# serial.net
KiCad netlist of a schematic drawn in EAGLE
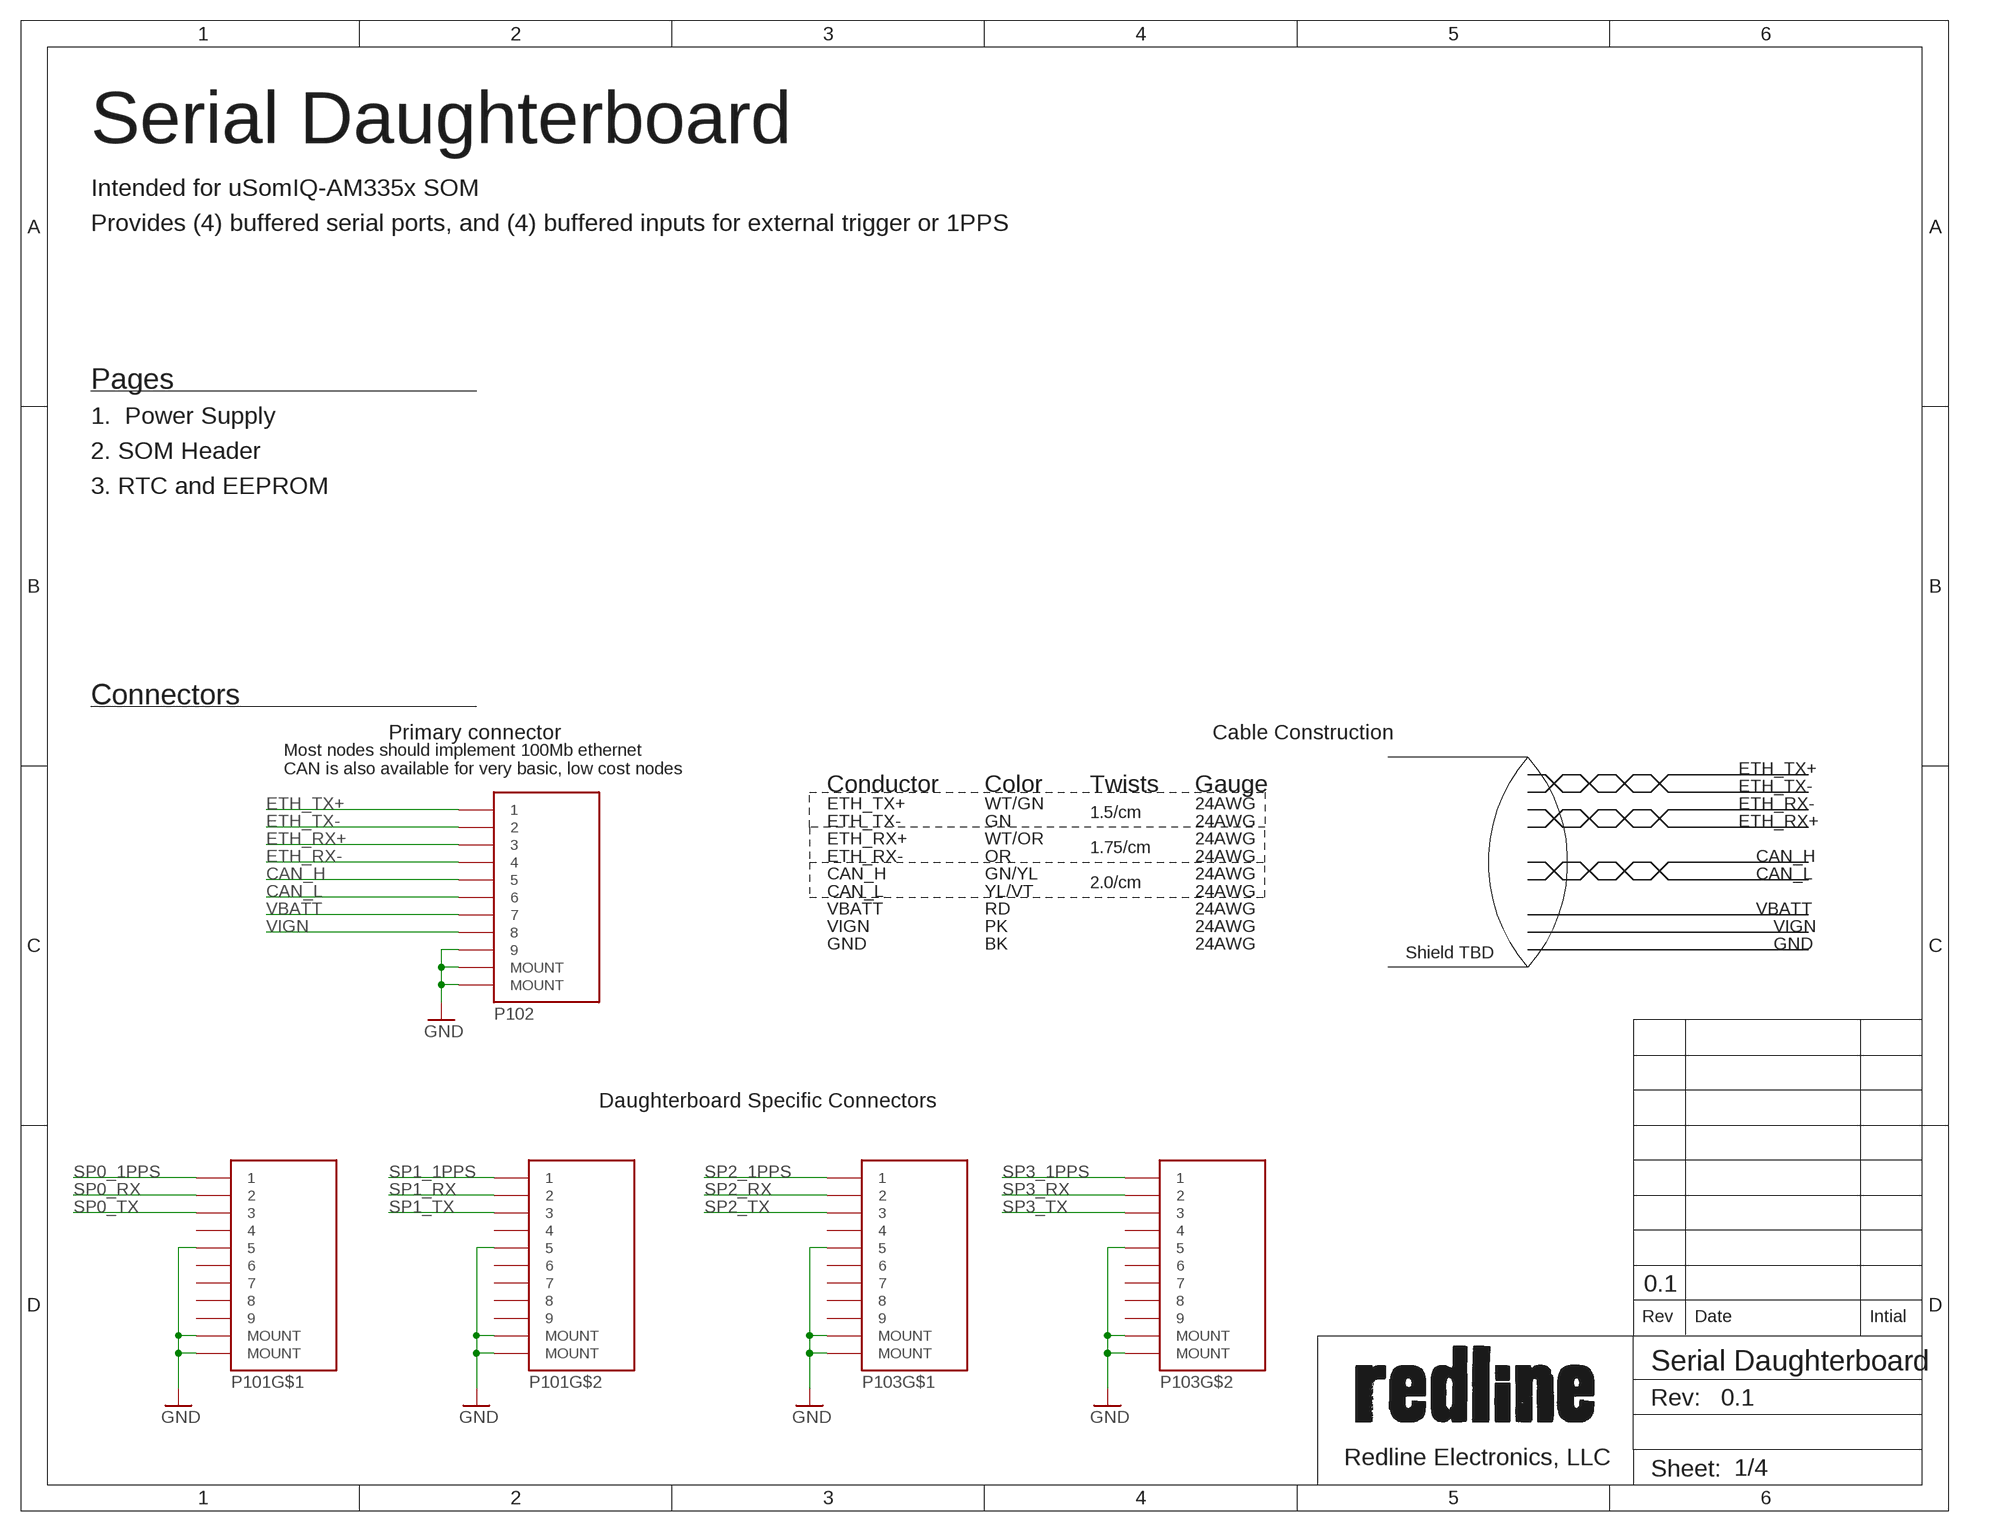
[diagram p0: schematic, sheet 1]
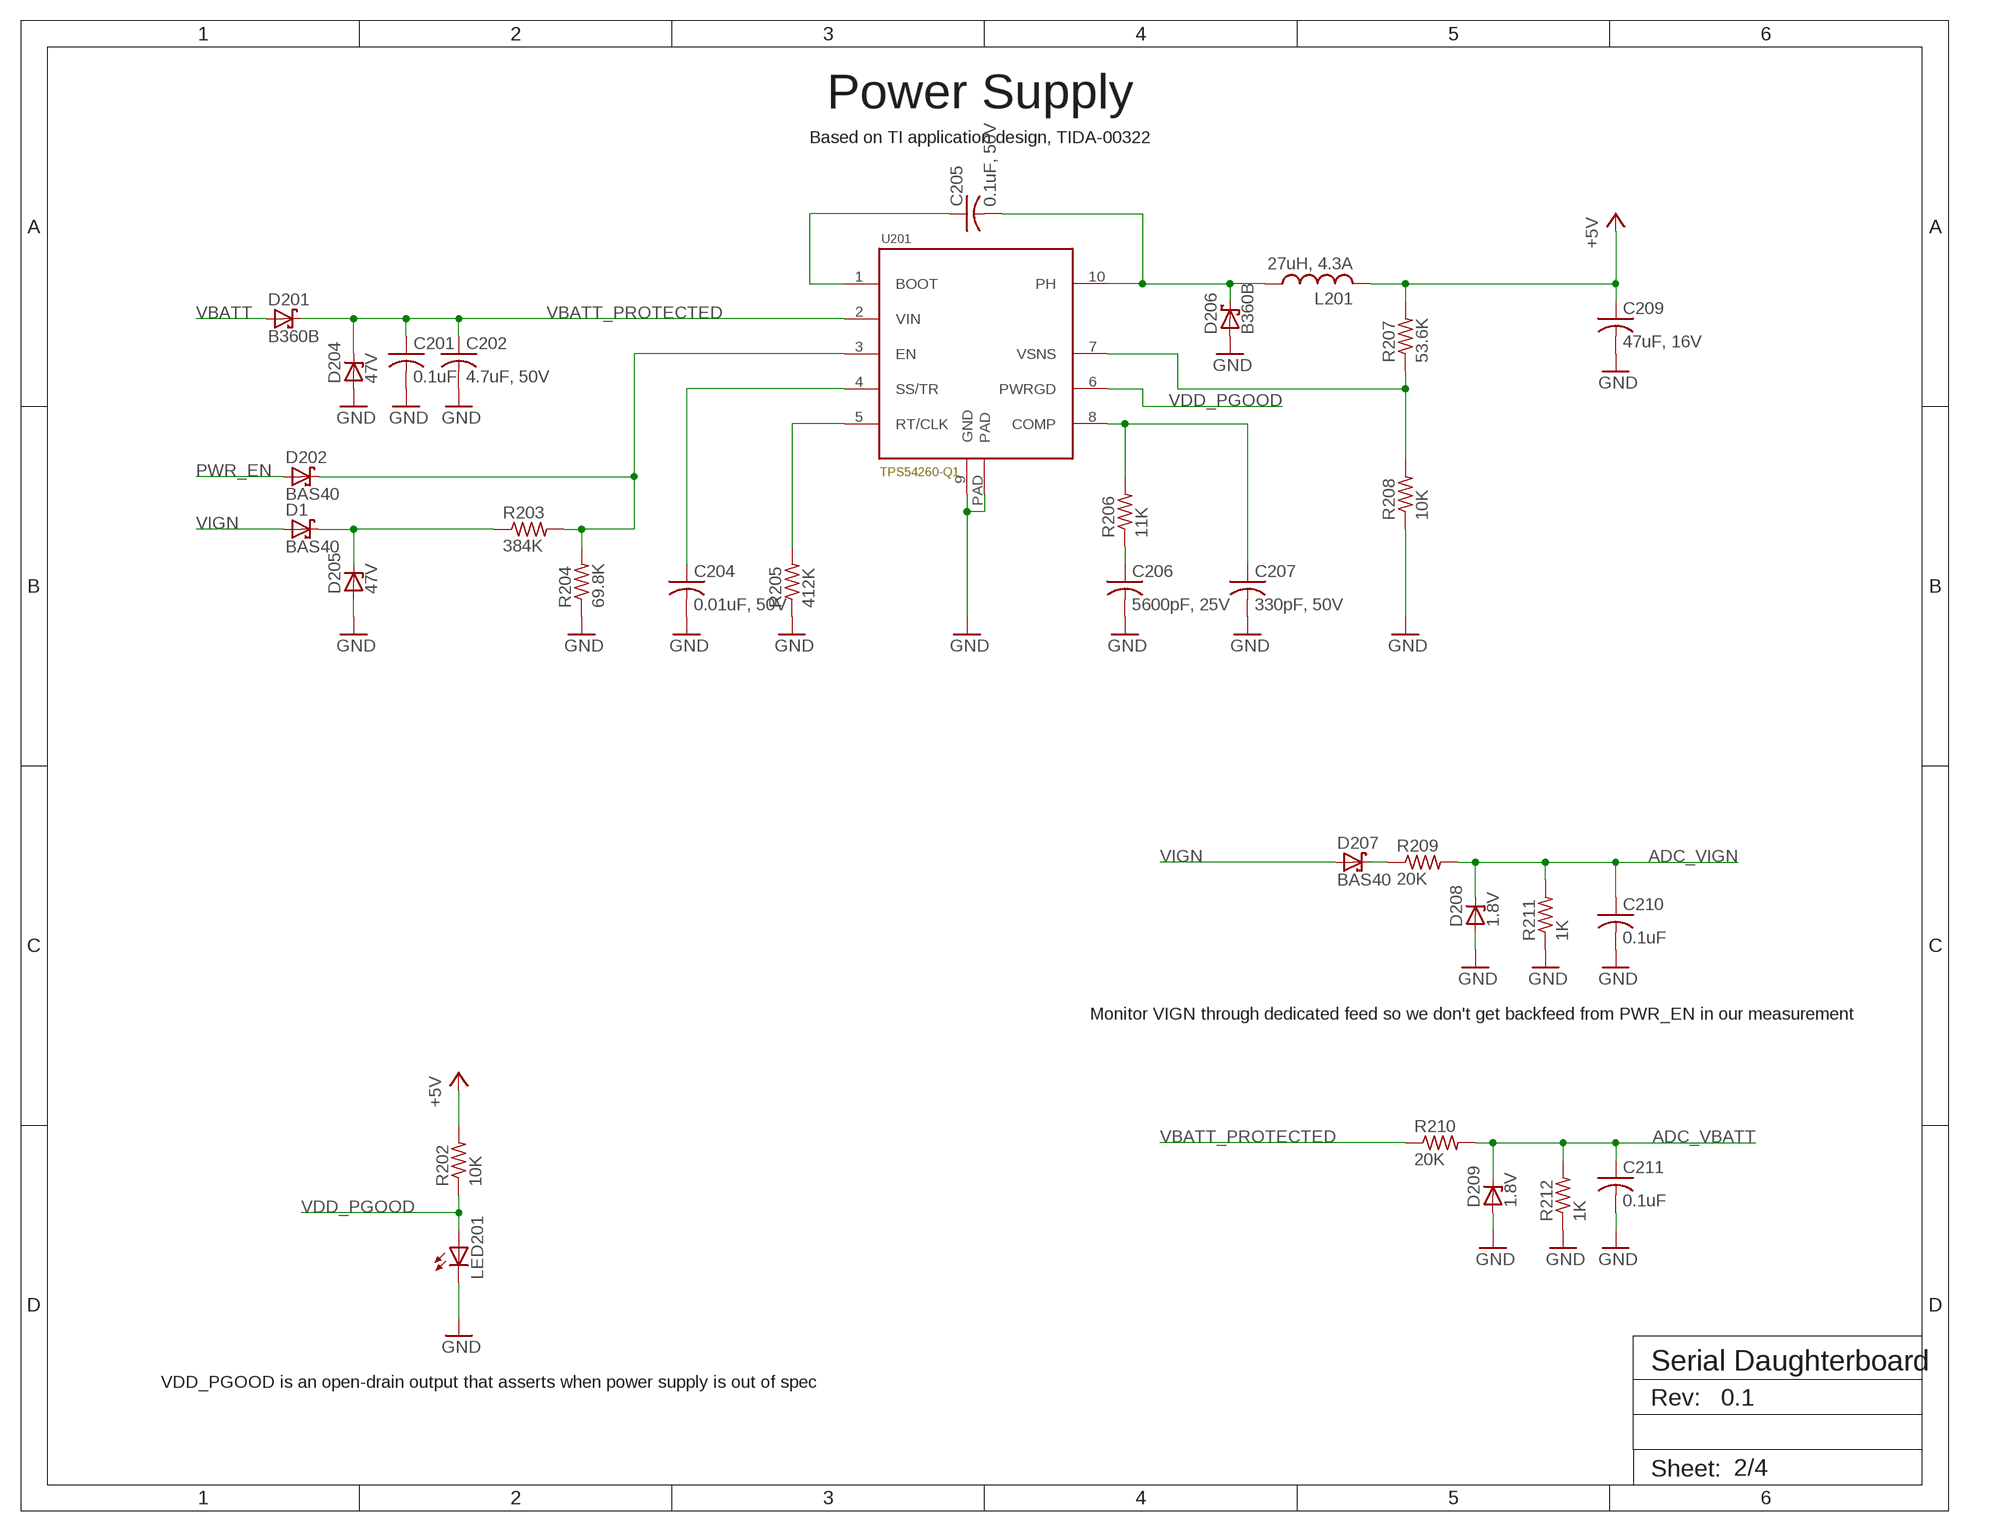
[diagram p1: schematic, sheet 2]
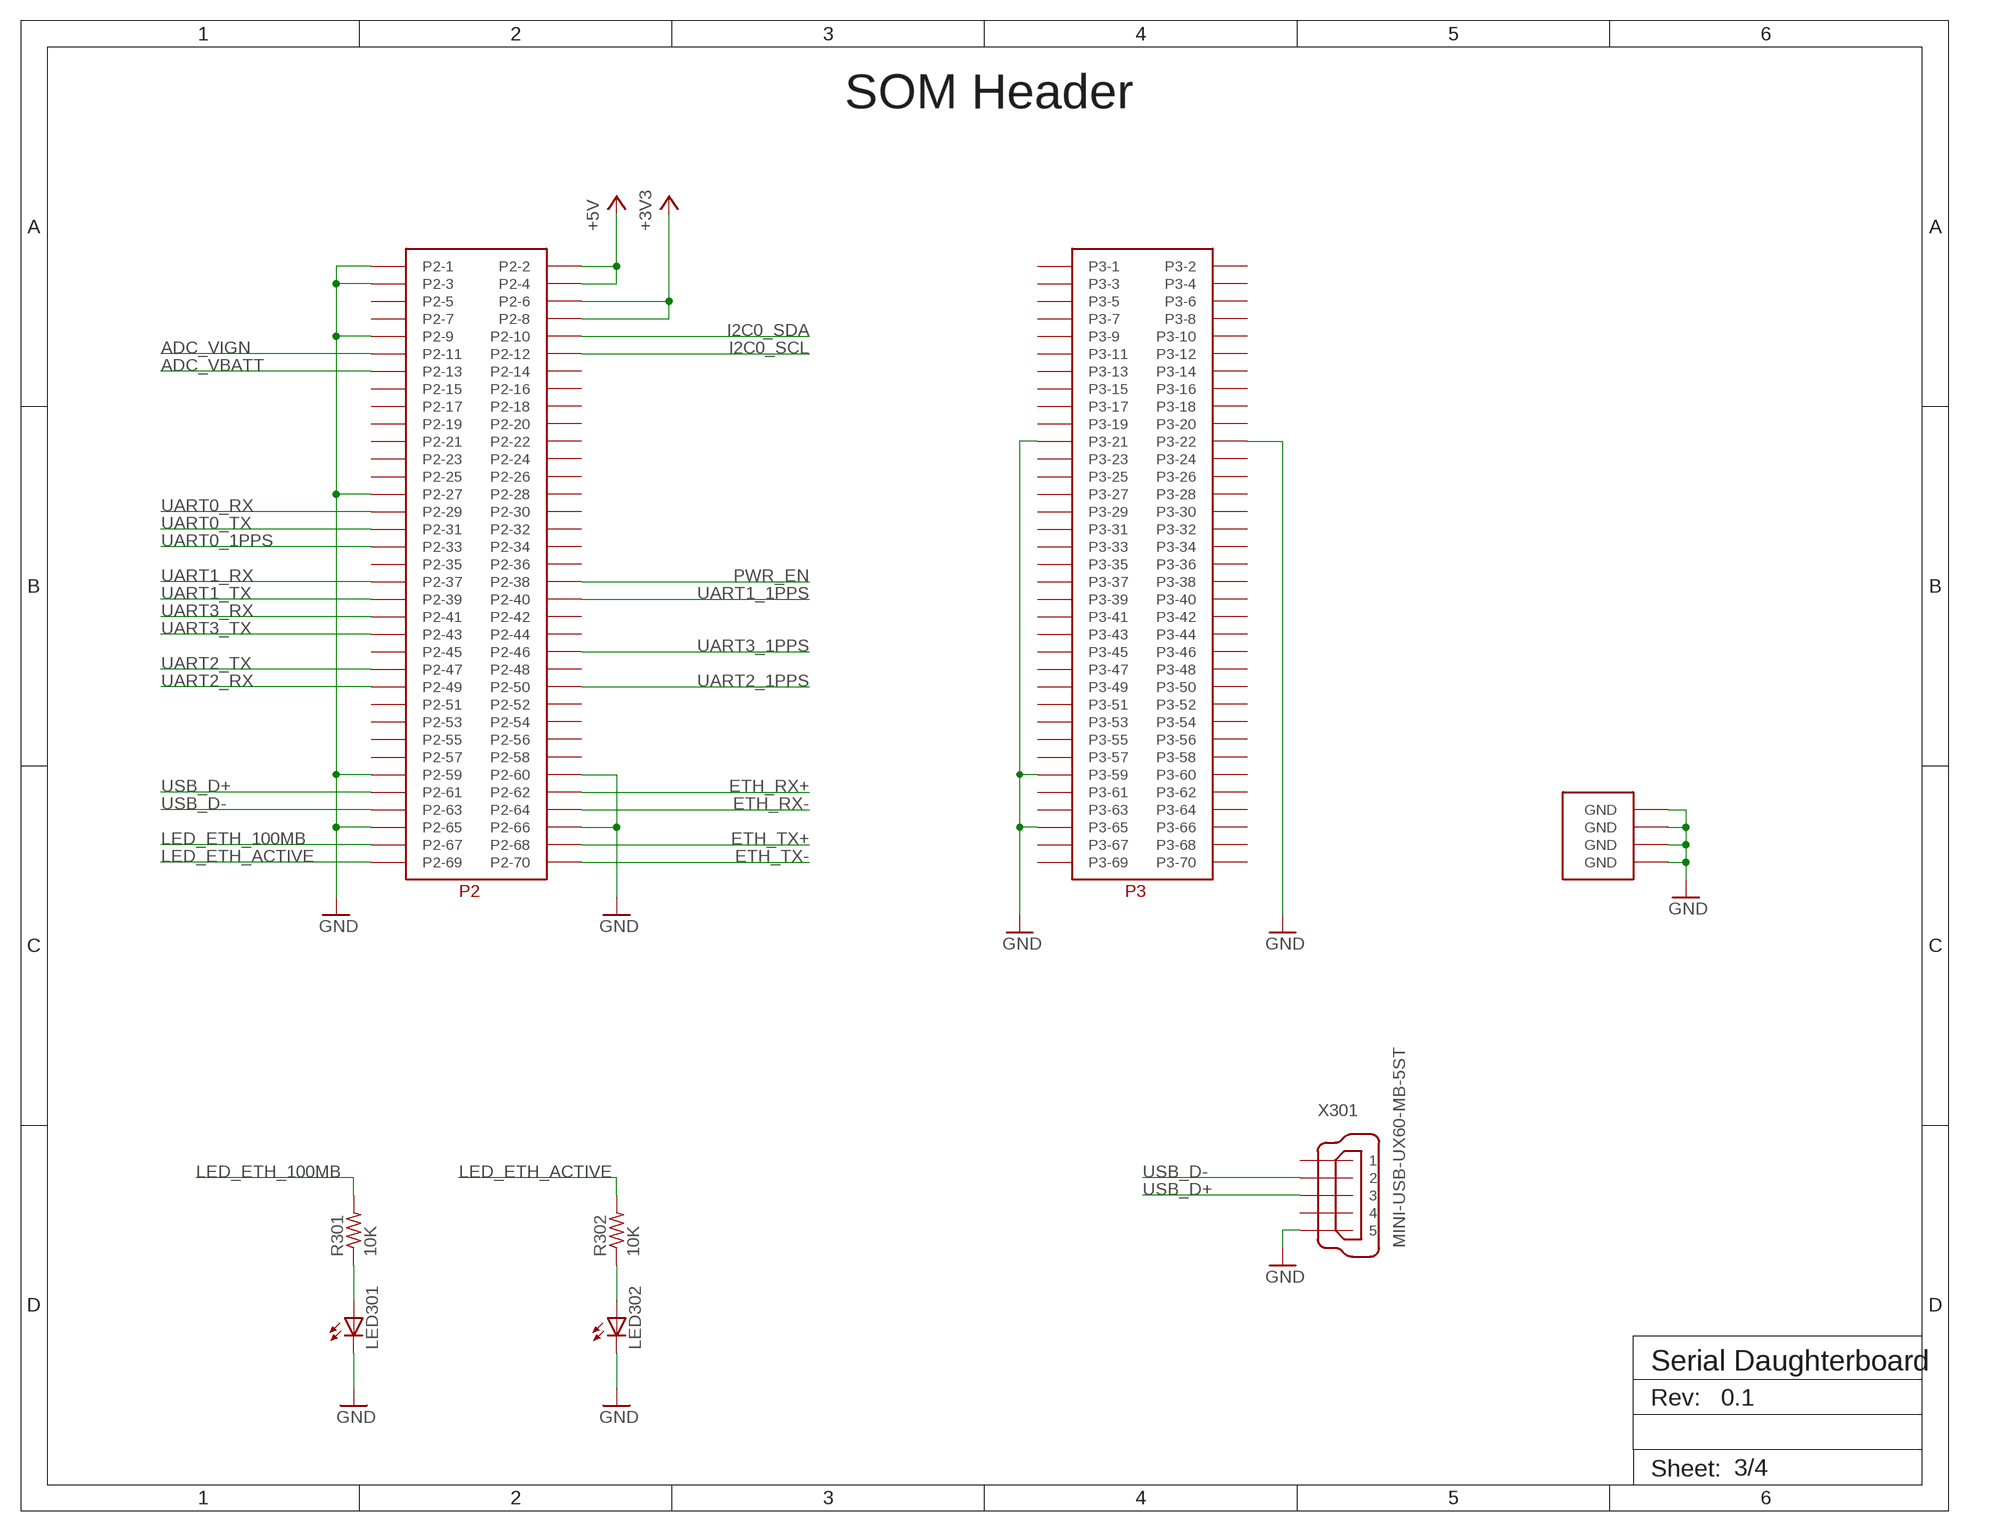
[diagram p2: schematic, sheet 3]
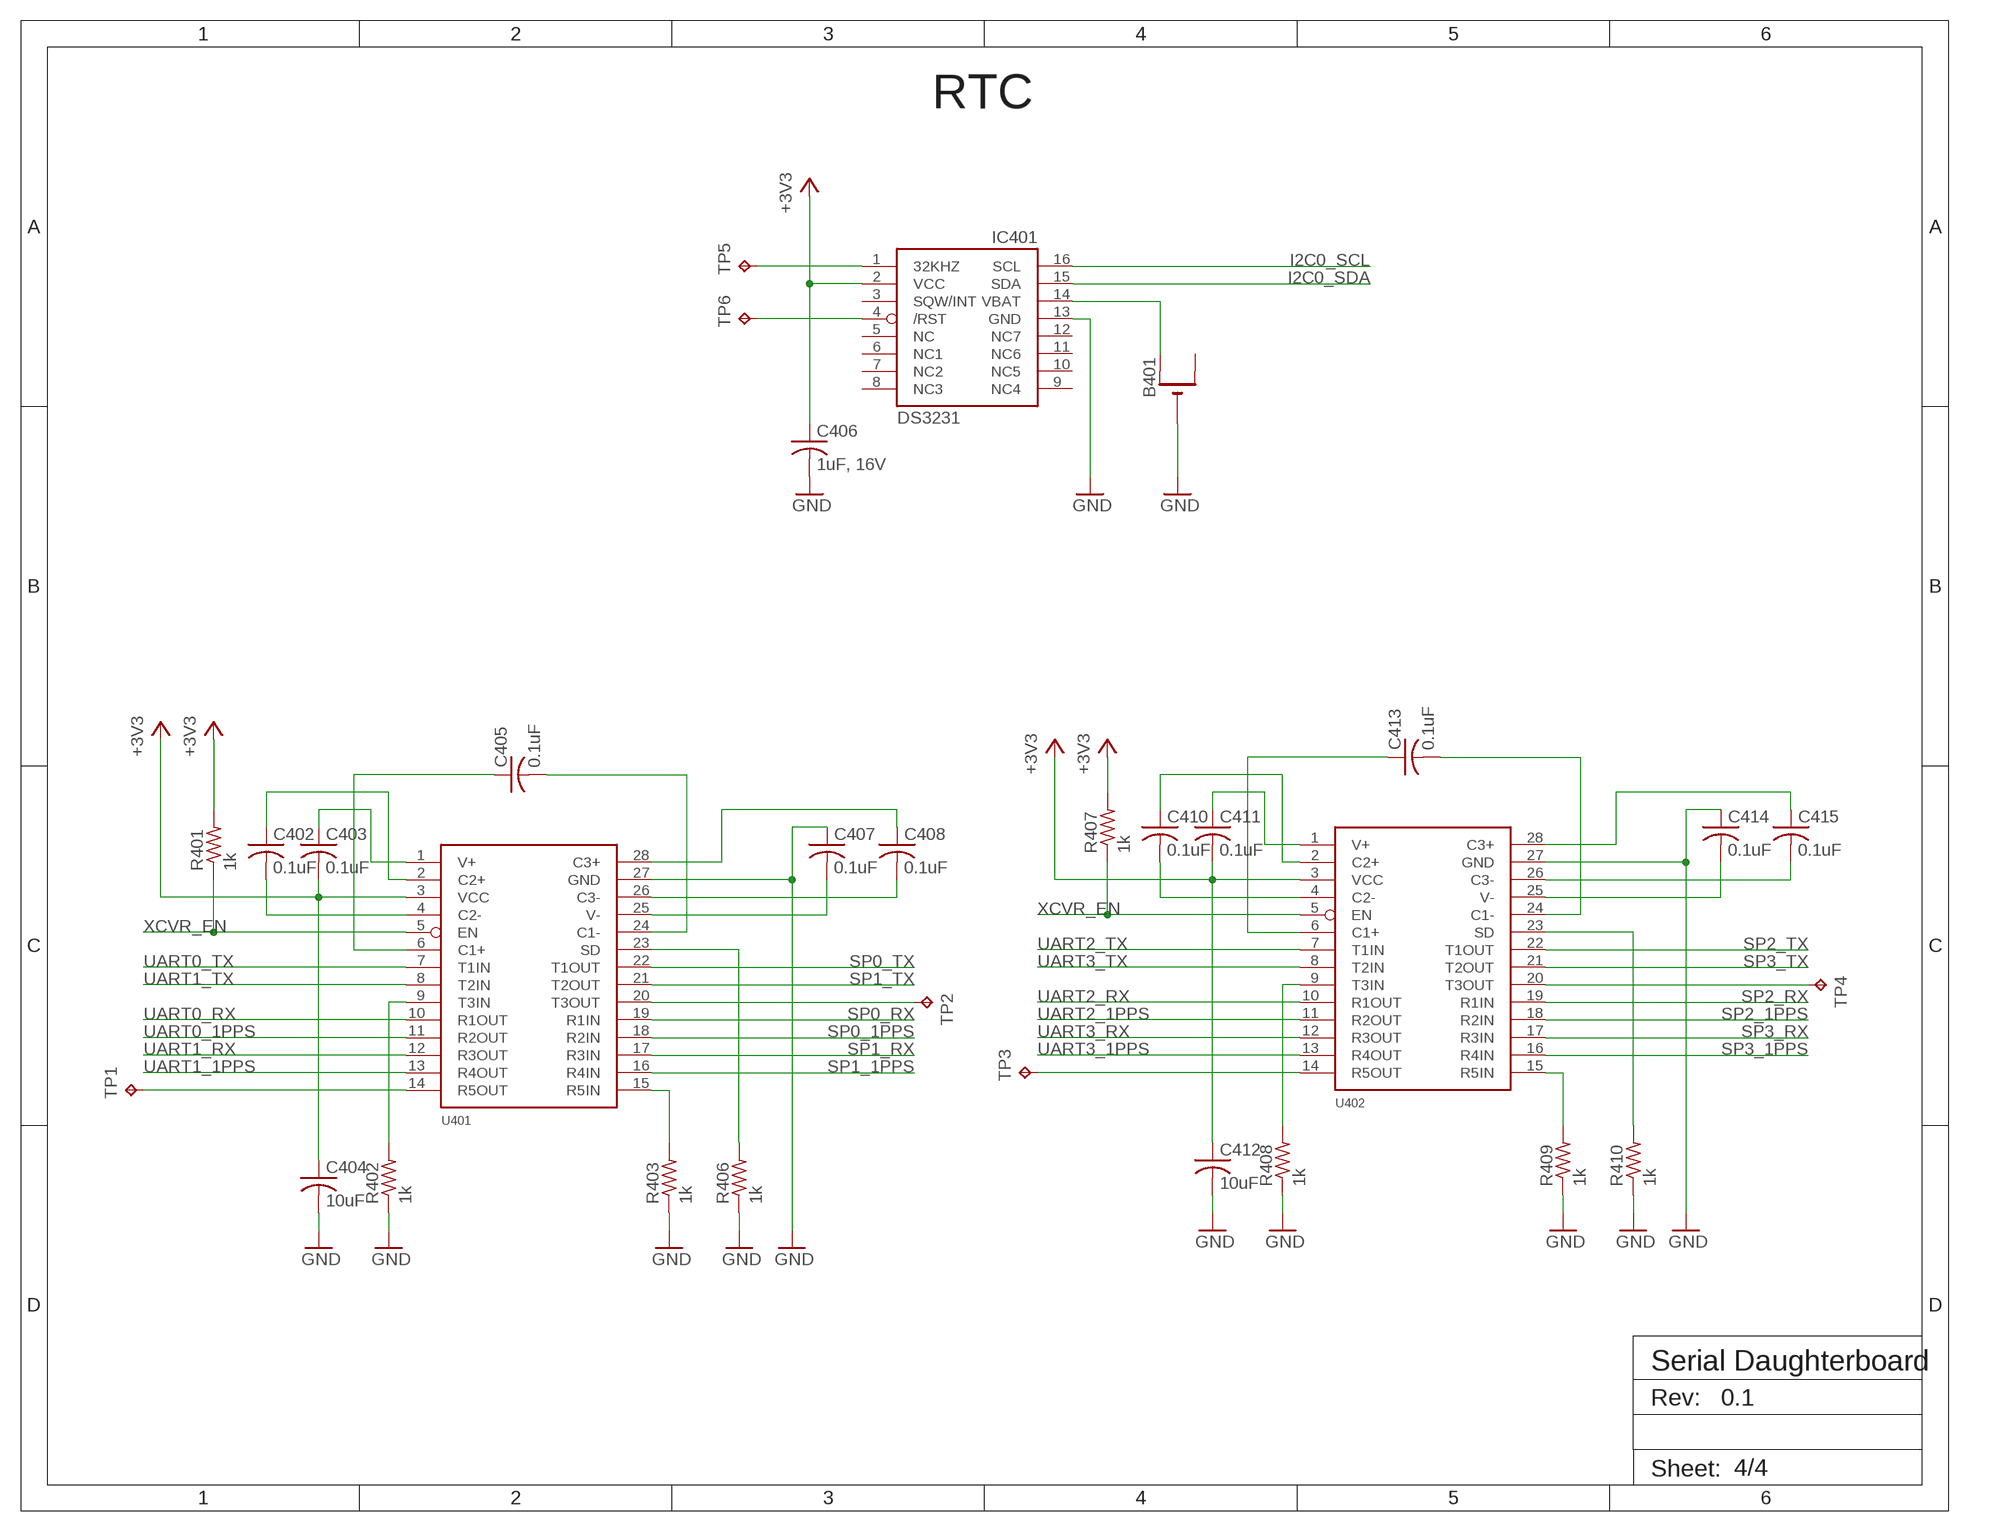
[diagram p3: schematic, sheet 4]

(export (version "E")
  (design (tool "Eeschema 10.0.6"))
  (components
    (comp (ref "LED301")
      (value "LEDSML0603")
      (footprint "eagle-import:SML0603")
      (libsource (lib "eagle-import") (part "LEDSML0603"))
    )
    (comp (ref "LED302")
      (value "LEDSML0603")
      (footprint "eagle-import:SML0603")
      (libsource (lib "eagle-import") (part "LEDSML0603"))
    )
    (comp (ref "P301")
      (value "USOMIQ-AM335X")
      (footprint "eagle-import:USOMIQ-AM335X")
      (libsource (lib "eagle-import") (part "USOMIQ-AM335X"))
    )
    (comp (ref "R301")
      (value "10K")
      (footprint "eagle-import:R0603")
      (libsource (lib "eagle-import") (part "R-US_R0603"))
    )
    (comp (ref "R302")
      (value "10K")
      (footprint "eagle-import:R0603")
      (libsource (lib "eagle-import") (part "R-US_R0603"))
    )
    (comp (ref "X301")
      (value "MINI-USB-UX60-MB-5ST")
      (footprint "eagle-import:UX60-MB-5ST")
      (libsource (lib "eagle-import") (part "MINI-USB-UX60-MB-5ST"))
    )
    (comp (ref "B401")
      (value "CR1220THM")
      (footprint "eagle-import:CR1220-THM")
      (libsource (lib "eagle-import") (part "CR1220THM"))
    )
    (comp (ref "C402")
      (value "0.1uF")
      (footprint "eagle-import:C0603")
      (libsource (lib "eagle-import") (part "resistor_C-USC0603"))
    )
    (comp (ref "C403")
      (value "0.1uF")
      (footprint "eagle-import:C0603")
      (libsource (lib "eagle-import") (part "resistor_C-USC0603"))
    )
    (comp (ref "C404")
      (value "10uF")
      (footprint "eagle-import:C0603")
      (libsource (lib "eagle-import") (part "resistor_C-USC0603"))
    )
    (comp (ref "C405")
      (value "0.1uF")
      (footprint "eagle-import:C0603")
      (libsource (lib "eagle-import") (part "resistor_C-USC0603"))
    )
    (comp (ref "C406")
      (value "1uF, 16V")
      (footprint "eagle-import:C0603")
      (libsource (lib "eagle-import") (part "C-USC0603"))
    )
    (comp (ref "C407")
      (value "0.1uF")
      (footprint "eagle-import:C0603")
      (libsource (lib "eagle-import") (part "resistor_C-USC0603"))
    )
    (comp (ref "C408")
      (value "0.1uF")
      (footprint "eagle-import:C0603")
      (libsource (lib "eagle-import") (part "resistor_C-USC0603"))
    )
    (comp (ref "C410")
      (value "0.1uF")
      (footprint "eagle-import:C0603")
      (libsource (lib "eagle-import") (part "resistor_C-USC0603"))
    )
    (comp (ref "C411")
      (value "0.1uF")
      (footprint "eagle-import:C0603")
      (libsource (lib "eagle-import") (part "resistor_C-USC0603"))
    )
    (comp (ref "C412")
      (value "10uF")
      (footprint "eagle-import:C0603")
      (libsource (lib "eagle-import") (part "resistor_C-USC0603"))
    )
    (comp (ref "C413")
      (value "0.1uF")
      (footprint "eagle-import:C0603")
      (libsource (lib "eagle-import") (part "resistor_C-USC0603"))
    )
    (comp (ref "C414")
      (value "0.1uF")
      (footprint "eagle-import:C0603")
      (libsource (lib "eagle-import") (part "resistor_C-USC0603"))
    )
    (comp (ref "C415")
      (value "0.1uF")
      (footprint "eagle-import:C0603")
      (libsource (lib "eagle-import") (part "resistor_C-USC0603"))
    )
    (comp (ref "IC401")
      (value "DS3231/SO")
      (footprint "eagle-import:SO16W")
      (libsource (lib "eagle-import") (part "DS3231/SO"))
    )
    (comp (ref "R401")
      (value "1k")
      (footprint "eagle-import:R0603")
      (libsource (lib "eagle-import") (part "resistor_R-US_R0603"))
    )
    (comp (ref "R402")
      (value "1k")
      (footprint "eagle-import:R0603")
      (libsource (lib "eagle-import") (part "resistor_R-US_R0603"))
    )
    (comp (ref "R403")
      (value "1k")
      (footprint "eagle-import:R0603")
      (libsource (lib "eagle-import") (part "resistor_R-US_R0603"))
    )
    (comp (ref "R406")
      (value "1k")
      (footprint "eagle-import:R0603")
      (libsource (lib "eagle-import") (part "resistor_R-US_R0603"))
    )
    (comp (ref "R407")
      (value "1k")
      (footprint "eagle-import:R0603")
      (libsource (lib "eagle-import") (part "resistor_R-US_R0603"))
    )
    (comp (ref "R408")
      (value "1k")
      (footprint "eagle-import:R0603")
      (libsource (lib "eagle-import") (part "resistor_R-US_R0603"))
    )
    (comp (ref "R409")
      (value "1k")
      (footprint "eagle-import:R0603")
      (libsource (lib "eagle-import") (part "resistor_R-US_R0603"))
    )
    (comp (ref "R410")
      (value "1k")
      (footprint "eagle-import:R0603")
      (libsource (lib "eagle-import") (part "resistor_R-US_R0603"))
    )
    (comp (ref "TP1")
      (value "TPB1,27")
      (footprint "eagle-import:B1,27")
      (libsource (lib "eagle-import") (part "TPB1,27"))
    )
    (comp (ref "TP2")
      (value "TPB1,27")
      (footprint "eagle-import:B1,27")
      (libsource (lib "eagle-import") (part "TPB1,27"))
    )
    (comp (ref "TP3")
      (value "TPB1,27")
      (footprint "eagle-import:B1,27")
      (libsource (lib "eagle-import") (part "TPB1,27"))
    )
    (comp (ref "TP4")
      (value "TPB1,27")
      (footprint "eagle-import:B1,27")
      (libsource (lib "eagle-import") (part "TPB1,27"))
    )
    (comp (ref "TP5")
      (value "TPB1,27")
      (footprint "eagle-import:B1,27")
      (libsource (lib "eagle-import") (part "TPB1,27"))
    )
    (comp (ref "TP6")
      (value "TPB1,27")
      (footprint "eagle-import:B1,27")
      (libsource (lib "eagle-import") (part "TPB1,27"))
    )
    (comp (ref "U401")
      (value "ADM3311E")
      (footprint "eagle-import:TSSOP28")
      (libsource (lib "eagle-import") (part "ADM3311E"))
    )
    (comp (ref "U402")
      (value "ADM3311E")
      (footprint "eagle-import:TSSOP28")
      (libsource (lib "eagle-import") (part "ADM3311E"))
    )
    (comp (ref "C201")
      (value "0.1uF")
      (footprint "eagle-import:C1210")
      (libsource (lib "eagle-import") (part "C-USC1210"))
    )
    (comp (ref "C202")
      (value "4.7uF, 50V")
      (footprint "eagle-import:C1210")
      (libsource (lib "eagle-import") (part "C-USC1210"))
    )
    (comp (ref "C204")
      (value "0.01uF, 50V")
      (footprint "eagle-import:C0603")
      (libsource (lib "eagle-import") (part "C-USC0603"))
    )
    (comp (ref "C205")
      (value "0.1uF, 50V")
      (footprint "eagle-import:C0603")
      (libsource (lib "eagle-import") (part "C-USC0603"))
    )
    (comp (ref "C206")
      (value "5600pF, 25V")
      (footprint "eagle-import:C0603")
      (libsource (lib "eagle-import") (part "C-USC0603"))
    )
    (comp (ref "C207")
      (value "330pF, 50V")
      (footprint "eagle-import:C0603")
      (libsource (lib "eagle-import") (part "C-USC0603"))
    )
    (comp (ref "C209")
      (value "47uF, 16V")
      (footprint "eagle-import:C2220K")
      (libsource (lib "eagle-import") (part "C-USC2220K"))
    )
    (comp (ref "C210")
      (value "0.1uF")
      (footprint "eagle-import:C0603")
      (libsource (lib "eagle-import") (part "C-USC0603"))
    )
    (comp (ref "C211")
      (value "0.1uF")
      (footprint "eagle-import:C0603")
      (libsource (lib "eagle-import") (part "C-USC0603"))
    )
    (comp (ref "D1")
      (value "BAS40")
      (footprint "eagle-import:SOT23")
      (libsource (lib "eagle-import") (part "BAS40"))
    )
    (comp (ref "D201")
      (value "B360B")
      (footprint "eagle-import:SMB")
      (libsource (lib "eagle-import") (part "SCHOTTKY-DIODESMD"))
    )
    (comp (ref "D202")
      (value "BAS40")
      (footprint "eagle-import:SOT23")
      (libsource (lib "eagle-import") (part "BAS40"))
    )
    (comp (ref "D204")
      (value "47V")
      (footprint "eagle-import:SMB")
      (libsource (lib "eagle-import") (part "ZENER-DIODESMB"))
    )
    (comp (ref "D205")
      (value "47V")
      (footprint "eagle-import:SOT23")
      (libsource (lib "eagle-import") (part "ZENER-DIODESOT23"))
    )
    (comp (ref "D206")
      (value "B360B")
      (footprint "eagle-import:SMB")
      (libsource (lib "eagle-import") (part "SCHOTTKY-DIODESMD"))
    )
    (comp (ref "D207")
      (value "BAS40")
      (footprint "eagle-import:SOT23")
      (libsource (lib "eagle-import") (part "BAS40"))
    )
    (comp (ref "D208")
      (value "1.8V")
      (footprint "eagle-import:SOT23")
      (libsource (lib "eagle-import") (part "ZENER-DIODESOT23"))
    )
    (comp (ref "D209")
      (value "1.8V")
      (footprint "eagle-import:SOT23")
      (libsource (lib "eagle-import") (part "ZENER-DIODESOT23"))
    )
    (comp (ref "L201")
      (value "27uH, 4.3A")
      (footprint "eagle-import:7447798271")
      (libsource (lib "eagle-import") (part "L-US"))
    )
    (comp (ref "LED201")
      (value "LEDSML0603")
      (footprint "eagle-import:SML0603")
      (libsource (lib "eagle-import") (part "LEDSML0603"))
    )
    (comp (ref "R202")
      (value "10K")
      (footprint "eagle-import:R0603")
      (libsource (lib "eagle-import") (part "R-US_R0603"))
    )
    (comp (ref "R203")
      (value "384K")
      (footprint "eagle-import:R0603")
      (libsource (lib "eagle-import") (part "R-US_R0603"))
    )
    (comp (ref "R204")
      (value "69.8K")
      (footprint "eagle-import:R0603")
      (libsource (lib "eagle-import") (part "R-US_R0603"))
    )
    (comp (ref "R205")
      (value "412K")
      (footprint "eagle-import:R0603")
      (libsource (lib "eagle-import") (part "R-US_R0603"))
    )
    (comp (ref "R206")
      (value "11K")
      (footprint "eagle-import:R0603")
      (libsource (lib "eagle-import") (part "R-US_R0603"))
    )
    (comp (ref "R207")
      (value "53.6K")
      (footprint "eagle-import:R0603")
      (libsource (lib "eagle-import") (part "R-US_R0603"))
    )
    (comp (ref "R208")
      (value "10K")
      (footprint "eagle-import:R0603")
      (libsource (lib "eagle-import") (part "R-US_R0603"))
    )
    (comp (ref "R209")
      (value "20K")
      (footprint "eagle-import:R0603")
      (libsource (lib "eagle-import") (part "R-US_R0603"))
    )
    (comp (ref "R210")
      (value "20K")
      (footprint "eagle-import:R0603")
      (libsource (lib "eagle-import") (part "R-US_R0603"))
    )
    (comp (ref "R211")
      (value "1K")
      (footprint "eagle-import:R0603")
      (libsource (lib "eagle-import") (part "R-US_R0603"))
    )
    (comp (ref "R212")
      (value "1K")
      (footprint "eagle-import:R0603")
      (libsource (lib "eagle-import") (part "R-US_R0603"))
    )
    (comp (ref "U201")
      (value "TPS54260")
      (footprint "eagle-import:S-PDSO-G10")
      (libsource (lib "eagle-import") (part "TPS54260"))
    )
    (comp (ref "P101")
      (value "189-009-613R571")
      (footprint "eagle-import:189-009-613R571")
      (libsource (lib "eagle-import") (part "189-009-613R571"))
    )
    (comp (ref "P102")
      (value "83611-9006")
      (footprint "eagle-import:83611-9006")
      (libsource (lib "eagle-import") (part "83611-9006"))
    )
    (comp (ref "P103")
      (value "189-009-613R571")
      (footprint "eagle-import:189-009-613R571")
      (libsource (lib "eagle-import") (part "189-009-613R571"))
    )
  )
  (nets
    (net (code "1") (name "+3V3") (class "Default")
      (node (ref "C403") (pin "2") (pinfunction "2_2") (pintype "passive"))
      (node (ref "C404") (pin "1") (pinfunction "1_1") (pintype "passive"))
      (node (ref "C406") (pin "1") (pinfunction "1_1") (pintype "passive"))
      (node (ref "C411") (pin "2") (pinfunction "2_2") (pintype "passive"))
      (node (ref "C412") (pin "1") (pinfunction "1_1") (pintype "passive"))
      (node (ref "IC401") (pin "2") (pinfunction "VCC_2") (pintype "power_in"))
      (node (ref "P301") (pin "P$6") (pinfunction "P2-6_P$6") (pintype "bidirectional"))
      (node (ref "P301") (pin "P$8") (pinfunction "P2-8_P$8") (pintype "bidirectional"))
      (node (ref "R401") (pin "2") (pinfunction "2_2") (pintype "passive"))
      (node (ref "R407") (pin "2") (pinfunction "2_2") (pintype "passive"))
      (node (ref "U401") (pin "3") (pinfunction "VCC_3") (pintype "bidirectional"))
      (node (ref "U402") (pin "3") (pinfunction "VCC_3") (pintype "bidirectional"))
    )
    (net (code "2") (name "+5V") (class "Default")
      (node (ref "C209") (pin "1") (pinfunction "1_1") (pintype "passive"))
      (node (ref "L201") (pin "P$2") (pinfunction "2_P$2") (pintype "passive"))
      (node (ref "P301") (pin "P$2") (pinfunction "P2-2_P$2") (pintype "bidirectional"))
      (node (ref "P301") (pin "P$4") (pinfunction "P2-4_P$4") (pintype "bidirectional"))
      (node (ref "R202") (pin "2") (pinfunction "2_2") (pintype "passive"))
      (node (ref "R207") (pin "2") (pinfunction "2_2") (pintype "passive"))
    )
    (net (code "3") (name "ADC_VBATT") (class "Default")
      (node (ref "C211") (pin "1") (pinfunction "1_1") (pintype "passive"))
      (node (ref "D209") (pin "3") (pinfunction "C_3") (pintype "passive"))
      (node (ref "P301") (pin "P$13") (pinfunction "P2-13_P$13") (pintype "bidirectional"))
      (node (ref "R210") (pin "2") (pinfunction "2_2") (pintype "passive"))
      (node (ref "R212") (pin "2") (pinfunction "2_2") (pintype "passive"))
    )
    (net (code "4") (name "ADC_VIGN") (class "Default")
      (node (ref "C210") (pin "1") (pinfunction "1_1") (pintype "passive"))
      (node (ref "D208") (pin "3") (pinfunction "C_3") (pintype "passive"))
      (node (ref "P301") (pin "P$11") (pinfunction "P2-11_P$11") (pintype "bidirectional"))
      (node (ref "R209") (pin "2") (pinfunction "2_2") (pintype "passive"))
      (node (ref "R211") (pin "2") (pinfunction "2_2") (pintype "passive"))
    )
    (net (code "5") (name "CAN_H") (class "Default")
      (node (ref "P102") (pin "5") (pinfunction "5_5") (pintype "bidirectional"))
    )
    (net (code "6") (name "CAN_L") (class "Default")
      (node (ref "P102") (pin "6") (pinfunction "6_6") (pintype "bidirectional"))
    )
    (net (code "7") (name "ETH_RX+") (class "Default")
      (node (ref "P102") (pin "3") (pinfunction "3_3") (pintype "bidirectional"))
      (node (ref "P301") (pin "P$62") (pinfunction "P2-62_P$62") (pintype "bidirectional"))
    )
    (net (code "8") (name "ETH_RX-") (class "Default")
      (node (ref "P102") (pin "4") (pinfunction "4_4") (pintype "bidirectional"))
      (node (ref "P301") (pin "P$64") (pinfunction "P2-64_P$64") (pintype "bidirectional"))
    )
    (net (code "9") (name "ETH_TX+") (class "Default")
      (node (ref "P102") (pin "1") (pinfunction "1_1") (pintype "bidirectional"))
      (node (ref "P301") (pin "P$68") (pinfunction "P2-68_P$68") (pintype "bidirectional"))
    )
    (net (code "10") (name "ETH_TX-") (class "Default")
      (node (ref "P102") (pin "2") (pinfunction "2_2") (pintype "bidirectional"))
      (node (ref "P301") (pin "P$70") (pinfunction "P2-70_P$70") (pintype "bidirectional"))
    )
    (net (code "11") (name "GND") (class "Default")
      (node (ref "B401") (pin "-") (pinfunction "-_-") (pintype "passive"))
      (node (ref "C201") (pin "2") (pinfunction "2_2") (pintype "passive"))
      (node (ref "C202") (pin "2") (pinfunction "2_2") (pintype "passive"))
      (node (ref "C204") (pin "2") (pinfunction "2_2") (pintype "passive"))
      (node (ref "C206") (pin "2") (pinfunction "2_2") (pintype "passive"))
      (node (ref "C207") (pin "2") (pinfunction "2_2") (pintype "passive"))
      (node (ref "C209") (pin "2") (pinfunction "2_2") (pintype "passive"))
      (node (ref "C210") (pin "2") (pinfunction "2_2") (pintype "passive"))
      (node (ref "C211") (pin "2") (pinfunction "2_2") (pintype "passive"))
      (node (ref "C404") (pin "2") (pinfunction "2_2") (pintype "passive"))
      (node (ref "C406") (pin "2") (pinfunction "2_2") (pintype "passive"))
      (node (ref "C407") (pin "1") (pinfunction "1_1") (pintype "passive"))
      (node (ref "C412") (pin "2") (pinfunction "2_2") (pintype "passive"))
      (node (ref "C414") (pin "1") (pinfunction "1_1") (pintype "passive"))
      (node (ref "D204") (pin "A") (pinfunction "A_A") (pintype "passive"))
      (node (ref "D205") (pin "1") (pinfunction "A_1") (pintype "passive"))
      (node (ref "D206") (pin "A") (pinfunction "A_A") (pintype "passive"))
      (node (ref "D208") (pin "1") (pinfunction "A_1") (pintype "passive"))
      (node (ref "D209") (pin "1") (pinfunction "A_1") (pintype "passive"))
      (node (ref "IC401") (pin "13") (pinfunction "GND_13") (pintype "power_in"))
      (node (ref "LED201") (pin "C") (pinfunction "C_C") (pintype "passive"))
      (node (ref "LED301") (pin "C") (pinfunction "C_C") (pintype "passive"))
      (node (ref "LED302") (pin "C") (pinfunction "C_C") (pintype "passive"))
      (node (ref "P101") (pin "A-5") (pinfunction "5_A-5") (pintype "bidirectional"))
      (node (ref "P101") (pin "B2") (pinfunction "5_B2") (pintype "bidirectional"))
      (node (ref "P101") (pin "MOUNT@1") (pinfunction "MOUNT_MOUNT@1") (pintype "bidirectional"))
      (node (ref "P101") (pin "MOUNT@2") (pinfunction "MOUNT_MOUNT@2") (pintype "bidirectional"))
      (node (ref "P101") (pin "MOUNT@3") (pinfunction "MOUNT_MOUNT@3") (pintype "bidirectional"))
      (node (ref "P101") (pin "MOUNT@4") (pinfunction "MOUNT_MOUNT@4") (pintype "bidirectional"))
      (node (ref "P102") (pin "9") (pinfunction "9_9") (pintype "bidirectional"))
      (node (ref "P102") (pin "MOUNT@1") (pinfunction "MOUNT_MOUNT@1") (pintype "bidirectional"))
      (node (ref "P102") (pin "MOUNT@2") (pinfunction "MOUNT_MOUNT@2") (pintype "bidirectional"))
      (node (ref "P103") (pin "A-5") (pinfunction "5_A-5") (pintype "bidirectional"))
      (node (ref "P103") (pin "B2") (pinfunction "5_B2") (pintype "bidirectional"))
      (node (ref "P103") (pin "MOUNT@1") (pinfunction "MOUNT_MOUNT@1") (pintype "bidirectional"))
      (node (ref "P103") (pin "MOUNT@2") (pinfunction "MOUNT_MOUNT@2") (pintype "bidirectional"))
      (node (ref "P103") (pin "MOUNT@3") (pinfunction "MOUNT_MOUNT@3") (pintype "bidirectional"))
      (node (ref "P103") (pin "MOUNT@4") (pinfunction "MOUNT_MOUNT@4") (pintype "bidirectional"))
      (node (ref "P301") (pin "MOUNT@0") (pinfunction "GND_MOUNT@0") (pintype "bidirectional"))
      (node (ref "P301") (pin "MOUNT@1") (pinfunction "GND_MOUNT@1") (pintype "bidirectional"))
      (node (ref "P301") (pin "MOUNT@2") (pinfunction "GND_MOUNT@2") (pintype "bidirectional"))
      (node (ref "P301") (pin "MOUNT@3") (pinfunction "GND_MOUNT@3") (pintype "bidirectional"))
      (node (ref "P301") (pin "P$1") (pinfunction "P2-1_P$1") (pintype "bidirectional"))
      (node (ref "P301") (pin "P$129") (pinfunction "P3-59_P$129") (pintype "bidirectional"))
      (node (ref "P301") (pin "P$135") (pinfunction "P3-65_P$135") (pintype "bidirectional"))
      (node (ref "P301") (pin "P$27") (pinfunction "P2-27_P$27") (pintype "bidirectional"))
      (node (ref "P301") (pin "P$3") (pinfunction "P2-3_P$3") (pintype "bidirectional"))
      (node (ref "P301") (pin "P$59") (pinfunction "P2-59_P$59") (pintype "bidirectional"))
      (node (ref "P301") (pin "P$60") (pinfunction "P2-60_P$60") (pintype "bidirectional"))
      (node (ref "P301") (pin "P$65") (pinfunction "P2-65_P$65") (pintype "bidirectional"))
      (node (ref "P301") (pin "P$66") (pinfunction "P2-66_P$66") (pintype "bidirectional"))
      (node (ref "P301") (pin "P$9") (pinfunction "P2-9_P$9") (pintype "bidirectional"))
      (node (ref "P301") (pin "P$91") (pinfunction "P3-21_P$91") (pintype "bidirectional"))
      (node (ref "P301") (pin "P$92") (pinfunction "P3-22_P$92") (pintype "bidirectional"))
      (node (ref "R204") (pin "1") (pinfunction "1_1") (pintype "passive"))
      (node (ref "R205") (pin "1") (pinfunction "1_1") (pintype "passive"))
      (node (ref "R208") (pin "1") (pinfunction "1_1") (pintype "passive"))
      (node (ref "R211") (pin "1") (pinfunction "1_1") (pintype "passive"))
      (node (ref "R212") (pin "1") (pinfunction "1_1") (pintype "passive"))
      (node (ref "R402") (pin "1") (pinfunction "1_1") (pintype "passive"))
      (node (ref "R403") (pin "1") (pinfunction "1_1") (pintype "passive"))
      (node (ref "R406") (pin "1") (pinfunction "1_1") (pintype "passive"))
      (node (ref "R408") (pin "1") (pinfunction "1_1") (pintype "passive"))
      (node (ref "R409") (pin "1") (pinfunction "1_1") (pintype "passive"))
      (node (ref "R410") (pin "1") (pinfunction "1_1") (pintype "passive"))
      (node (ref "U201") (pin "9") (pinfunction "GND_9") (pintype "bidirectional"))
      (node (ref "U201") (pin "PAD") (pinfunction "PAD_PAD") (pintype "bidirectional"))
      (node (ref "U401") (pin "27") (pinfunction "GND_27") (pintype "bidirectional"))
      (node (ref "U402") (pin "27") (pinfunction "GND_27") (pintype "bidirectional"))
      (node (ref "X301") (pin "5") (pinfunction "5_5") (pintype "input"))
    )
    (net (code "12") (name "I2C0_SCL") (class "Default")
      (node (ref "IC401") (pin "16") (pinfunction "SCL_16") (pintype "bidirectional"))
      (node (ref "P301") (pin "P$12") (pinfunction "P2-12_P$12") (pintype "bidirectional"))
    )
    (net (code "13") (name "I2C0_SDA") (class "Default")
      (node (ref "IC401") (pin "15") (pinfunction "SDA_15") (pintype "bidirectional"))
      (node (ref "P301") (pin "P$10") (pinfunction "P2-10_P$10") (pintype "bidirectional"))
    )
    (net (code "14") (name "LED_ETH_100MB") (class "Default")
      (node (ref "P301") (pin "P$67") (pinfunction "P2-67_P$67") (pintype "bidirectional"))
      (node (ref "R301") (pin "2") (pinfunction "2_2") (pintype "passive"))
    )
    (net (code "15") (name "LED_ETH_ACTIVE") (class "Default")
      (node (ref "P301") (pin "P$69") (pinfunction "P2-69_P$69") (pintype "bidirectional"))
      (node (ref "R302") (pin "2") (pinfunction "2_2") (pintype "passive"))
    )
    (net (code "16") (name "Net-(B401-+)") (class "Default")
      (node (ref "B401") (pin "+1") (pinfunction "+_+1") (pintype "passive"))
      (node (ref "IC401") (pin "14") (pinfunction "VBAT_14") (pintype "power_in"))
    )
    (net (code "17") (name "Net-(C206-Pad1)") (class "Default")
      (node (ref "C206") (pin "1") (pinfunction "1_1") (pintype "passive"))
      (node (ref "R206") (pin "1") (pinfunction "1_1") (pintype "passive"))
    )
    (net (code "18") (name "Net-(D1-C)") (class "Default")
      (node (ref "D1") (pin "3") (pinfunction "C_3") (pintype "passive"))
      (node (ref "D205") (pin "3") (pinfunction "C_3") (pintype "passive"))
      (node (ref "R203") (pin "1") (pinfunction "1_1") (pintype "passive"))
    )
    (net (code "19") (name "Net-(D202-C)") (class "Default")
      (node (ref "D202") (pin "3") (pinfunction "C_3") (pintype "passive"))
      (node (ref "R203") (pin "2") (pinfunction "2_2") (pintype "passive"))
      (node (ref "R204") (pin "2") (pinfunction "2_2") (pintype "passive"))
      (node (ref "U201") (pin "3") (pinfunction "EN_3") (pintype "bidirectional"))
    )
    (net (code "20") (name "Net-(D207-C)") (class "Default")
      (node (ref "D207") (pin "3") (pinfunction "C_3") (pintype "passive"))
      (node (ref "R209") (pin "1") (pinfunction "1_1") (pintype "passive"))
    )
    (net (code "21") (name "Net-(IC401-32KHZ)") (class "Default")
      (node (ref "IC401") (pin "1") (pinfunction "32KHZ_1") (pintype "output"))
      (node (ref "TP5") (pin "TP") (pinfunction "TP_TP") (pintype "input"))
    )
    (net (code "22") (name "Net-(IC401-{slash}RST)") (class "Default")
      (node (ref "IC401") (pin "4") (pinfunction "/RST_4") (pintype "passive"))
      (node (ref "TP6") (pin "TP") (pinfunction "TP_TP") (pintype "input"))
    )
    (net (code "23") (name "Net-(L201-1)") (class "Default")
      (node (ref "C205") (pin "2") (pinfunction "2_2") (pintype "passive"))
      (node (ref "D206") (pin "C") (pinfunction "C_C") (pintype "passive"))
      (node (ref "L201") (pin "P$1") (pinfunction "1_P$1") (pintype "passive"))
      (node (ref "U201") (pin "10") (pinfunction "PH_10") (pintype "bidirectional"))
    )
    (net (code "24") (name "Net-(LED301-PadA)") (class "Default")
      (node (ref "LED301") (pin "A") (pinfunction "A_A") (pintype "passive"))
      (node (ref "R301") (pin "1") (pinfunction "1_1") (pintype "passive"))
    )
    (net (code "25") (name "Net-(LED302-PadA)") (class "Default")
      (node (ref "LED302") (pin "A") (pinfunction "A_A") (pintype "passive"))
      (node (ref "R302") (pin "1") (pinfunction "1_1") (pintype "passive"))
    )
    (net (code "26") (name "Net-(U201-BOOT)") (class "Default")
      (node (ref "C205") (pin "1") (pinfunction "1_1") (pintype "passive"))
      (node (ref "U201") (pin "1") (pinfunction "BOOT_1") (pintype "bidirectional"))
    )
    (net (code "27") (name "Net-(U201-COMP)") (class "Default")
      (node (ref "C207") (pin "1") (pinfunction "1_1") (pintype "passive"))
      (node (ref "R206") (pin "2") (pinfunction "2_2") (pintype "passive"))
      (node (ref "U201") (pin "8") (pinfunction "COMP_8") (pintype "bidirectional"))
    )
    (net (code "28") (name "Net-(U201-RT{slash}CLK)") (class "Default")
      (node (ref "R205") (pin "2") (pinfunction "2_2") (pintype "passive"))
      (node (ref "U201") (pin "5") (pinfunction "RT/CLK_5") (pintype "bidirectional"))
    )
    (net (code "29") (name "Net-(U201-SS{slash}TR)") (class "Default")
      (node (ref "C204") (pin "1") (pinfunction "1_1") (pintype "passive"))
      (node (ref "U201") (pin "4") (pinfunction "SS/TR_4") (pintype "bidirectional"))
    )
    (net (code "30") (name "Net-(U201-VSNS)") (class "Default")
      (node (ref "R207") (pin "1") (pinfunction "1_1") (pintype "passive"))
      (node (ref "R208") (pin "2") (pinfunction "2_2") (pintype "passive"))
      (node (ref "U201") (pin "7") (pinfunction "VSNS_7") (pintype "bidirectional"))
    )
    (net (code "31") (name "Net-(U401-C1+)") (class "Default")
      (node (ref "C405") (pin "1") (pinfunction "1_1") (pintype "passive"))
      (node (ref "U401") (pin "6") (pinfunction "C1+_6") (pintype "bidirectional"))
    )
    (net (code "32") (name "Net-(U401-C1-)") (class "Default")
      (node (ref "C405") (pin "2") (pinfunction "2_2") (pintype "passive"))
      (node (ref "U401") (pin "24") (pinfunction "C1-_24") (pintype "bidirectional"))
    )
    (net (code "33") (name "Net-(U401-C2+)") (class "Default")
      (node (ref "C402") (pin "1") (pinfunction "1_1") (pintype "passive"))
      (node (ref "U401") (pin "2") (pinfunction "C2+_2") (pintype "bidirectional"))
    )
    (net (code "34") (name "Net-(U401-C2-)") (class "Default")
      (node (ref "C402") (pin "2") (pinfunction "2_2") (pintype "passive"))
      (node (ref "U401") (pin "4") (pinfunction "C2-_4") (pintype "bidirectional"))
    )
    (net (code "35") (name "Net-(U401-C3+)") (class "Default")
      (node (ref "C408") (pin "1") (pinfunction "1_1") (pintype "passive"))
      (node (ref "U401") (pin "28") (pinfunction "C3+_28") (pintype "bidirectional"))
    )
    (net (code "36") (name "Net-(U401-C3-)") (class "Default")
      (node (ref "C408") (pin "2") (pinfunction "2_2") (pintype "passive"))
      (node (ref "U401") (pin "26") (pinfunction "C3-_26") (pintype "bidirectional"))
    )
    (net (code "37") (name "Net-(U401-R5IN)") (class "Default")
      (node (ref "R403") (pin "2") (pinfunction "2_2") (pintype "passive"))
      (node (ref "U401") (pin "15") (pinfunction "R5IN_15") (pintype "bidirectional"))
    )
    (net (code "38") (name "Net-(U401-R5OUT)") (class "Default")
      (node (ref "TP1") (pin "TP") (pinfunction "TP_TP") (pintype "input"))
      (node (ref "U401") (pin "14") (pinfunction "R5OUT_14") (pintype "bidirectional"))
    )
    (net (code "39") (name "Net-(U401-SD)") (class "Default")
      (node (ref "R406") (pin "2") (pinfunction "2_2") (pintype "passive"))
      (node (ref "U401") (pin "23") (pinfunction "SD_23") (pintype "bidirectional"))
    )
    (net (code "40") (name "Net-(U401-T3IN)") (class "Default")
      (node (ref "R402") (pin "2") (pinfunction "2_2") (pintype "passive"))
      (node (ref "U401") (pin "9") (pinfunction "T3IN_9") (pintype "bidirectional"))
    )
    (net (code "41") (name "Net-(U401-T3OUT)") (class "Default")
      (node (ref "TP2") (pin "TP") (pinfunction "TP_TP") (pintype "input"))
      (node (ref "U401") (pin "20") (pinfunction "T3OUT_20") (pintype "bidirectional"))
    )
    (net (code "42") (name "Net-(U401-V+)") (class "Default")
      (node (ref "C403") (pin "1") (pinfunction "1_1") (pintype "passive"))
      (node (ref "U401") (pin "1") (pinfunction "V+_1") (pintype "bidirectional"))
    )
    (net (code "43") (name "Net-(U401-V-)") (class "Default")
      (node (ref "C407") (pin "2") (pinfunction "2_2") (pintype "passive"))
      (node (ref "U401") (pin "25") (pinfunction "V-_25") (pintype "bidirectional"))
    )
    (net (code "44") (name "Net-(U402-C1+)") (class "Default")
      (node (ref "C413") (pin "1") (pinfunction "1_1") (pintype "passive"))
      (node (ref "U402") (pin "6") (pinfunction "C1+_6") (pintype "bidirectional"))
    )
    (net (code "45") (name "Net-(U402-C1-)") (class "Default")
      (node (ref "C413") (pin "2") (pinfunction "2_2") (pintype "passive"))
      (node (ref "U402") (pin "24") (pinfunction "C1-_24") (pintype "bidirectional"))
    )
    (net (code "46") (name "Net-(U402-C2+)") (class "Default")
      (node (ref "C410") (pin "1") (pinfunction "1_1") (pintype "passive"))
      (node (ref "U402") (pin "2") (pinfunction "C2+_2") (pintype "bidirectional"))
    )
    (net (code "47") (name "Net-(U402-C2-)") (class "Default")
      (node (ref "C410") (pin "2") (pinfunction "2_2") (pintype "passive"))
      (node (ref "U402") (pin "4") (pinfunction "C2-_4") (pintype "bidirectional"))
    )
    (net (code "48") (name "Net-(U402-C3+)") (class "Default")
      (node (ref "C415") (pin "1") (pinfunction "1_1") (pintype "passive"))
      (node (ref "U402") (pin "28") (pinfunction "C3+_28") (pintype "bidirectional"))
    )
    (net (code "49") (name "Net-(U402-C3-)") (class "Default")
      (node (ref "C415") (pin "2") (pinfunction "2_2") (pintype "passive"))
      (node (ref "U402") (pin "26") (pinfunction "C3-_26") (pintype "bidirectional"))
    )
    (net (code "50") (name "Net-(U402-R5IN)") (class "Default")
      (node (ref "R409") (pin "2") (pinfunction "2_2") (pintype "passive"))
      (node (ref "U402") (pin "15") (pinfunction "R5IN_15") (pintype "bidirectional"))
    )
    (net (code "51") (name "Net-(U402-R5OUT)") (class "Default")
      (node (ref "TP3") (pin "TP") (pinfunction "TP_TP") (pintype "input"))
      (node (ref "U402") (pin "14") (pinfunction "R5OUT_14") (pintype "bidirectional"))
    )
    (net (code "52") (name "Net-(U402-SD)") (class "Default")
      (node (ref "R410") (pin "2") (pinfunction "2_2") (pintype "passive"))
      (node (ref "U402") (pin "23") (pinfunction "SD_23") (pintype "bidirectional"))
    )
    (net (code "53") (name "Net-(U402-T3IN)") (class "Default")
      (node (ref "R408") (pin "2") (pinfunction "2_2") (pintype "passive"))
      (node (ref "U402") (pin "9") (pinfunction "T3IN_9") (pintype "bidirectional"))
    )
    (net (code "54") (name "Net-(U402-T3OUT)") (class "Default")
      (node (ref "TP4") (pin "TP") (pinfunction "TP_TP") (pintype "input"))
      (node (ref "U402") (pin "20") (pinfunction "T3OUT_20") (pintype "bidirectional"))
    )
    (net (code "55") (name "Net-(U402-V+)") (class "Default")
      (node (ref "C411") (pin "1") (pinfunction "1_1") (pintype "passive"))
      (node (ref "U402") (pin "1") (pinfunction "V+_1") (pintype "bidirectional"))
    )
    (net (code "56") (name "Net-(U402-V-)") (class "Default")
      (node (ref "C414") (pin "2") (pinfunction "2_2") (pintype "passive"))
      (node (ref "U402") (pin "25") (pinfunction "V-_25") (pintype "bidirectional"))
    )
    (net (code "57") (name "PWR_EN") (class "Default")
      (node (ref "D202") (pin "1") (pinfunction "A_1") (pintype "passive"))
      (node (ref "P301") (pin "P$38") (pinfunction "P2-38_P$38") (pintype "bidirectional"))
    )
    (net (code "58") (name "SP0_1PPS") (class "Default")
      (node (ref "P101") (pin "A-1") (pinfunction "1_A-1") (pintype "bidirectional"))
      (node (ref "U401") (pin "18") (pinfunction "R2IN_18") (pintype "bidirectional"))
    )
    (net (code "59") (name "SP0_RX") (class "Default")
      (node (ref "P101") (pin "A-2") (pinfunction "2_A-2") (pintype "bidirectional"))
      (node (ref "U401") (pin "19") (pinfunction "R1IN_19") (pintype "bidirectional"))
    )
    (net (code "60") (name "SP0_TX") (class "Default")
      (node (ref "P101") (pin "A-3") (pinfunction "3_A-3") (pintype "bidirectional"))
      (node (ref "U401") (pin "22") (pinfunction "T1OUT_22") (pintype "bidirectional"))
    )
    (net (code "61") (name "SP1_1PPS") (class "Default")
      (node (ref "P101") (pin "B-1") (pinfunction "1_B-1") (pintype "bidirectional"))
      (node (ref "U401") (pin "16") (pinfunction "R4IN_16") (pintype "bidirectional"))
    )
    (net (code "62") (name "SP1_RX") (class "Default")
      (node (ref "P101") (pin "B-3") (pinfunction "2_B-3") (pintype "bidirectional"))
      (node (ref "U401") (pin "17") (pinfunction "R3IN_17") (pintype "bidirectional"))
    )
    (net (code "63") (name "SP1_TX") (class "Default")
      (node (ref "P101") (pin "B-4") (pinfunction "3_B-4") (pintype "bidirectional"))
      (node (ref "U401") (pin "21") (pinfunction "T2OUT_21") (pintype "bidirectional"))
    )
    (net (code "64") (name "SP2_1PPS") (class "Default")
      (node (ref "P103") (pin "A-1") (pinfunction "1_A-1") (pintype "bidirectional"))
      (node (ref "U402") (pin "18") (pinfunction "R2IN_18") (pintype "bidirectional"))
    )
    (net (code "65") (name "SP2_RX") (class "Default")
      (node (ref "P103") (pin "A-2") (pinfunction "2_A-2") (pintype "bidirectional"))
      (node (ref "U402") (pin "19") (pinfunction "R1IN_19") (pintype "bidirectional"))
    )
    (net (code "66") (name "SP2_TX") (class "Default")
      (node (ref "P103") (pin "A-3") (pinfunction "3_A-3") (pintype "bidirectional"))
      (node (ref "U402") (pin "22") (pinfunction "T1OUT_22") (pintype "bidirectional"))
    )
    (net (code "67") (name "SP3_1PPS") (class "Default")
      (node (ref "P103") (pin "B-1") (pinfunction "1_B-1") (pintype "bidirectional"))
      (node (ref "U402") (pin "16") (pinfunction "R4IN_16") (pintype "bidirectional"))
    )
    (net (code "68") (name "SP3_RX") (class "Default")
      (node (ref "P103") (pin "B-3") (pinfunction "2_B-3") (pintype "bidirectional"))
      (node (ref "U402") (pin "17") (pinfunction "R3IN_17") (pintype "bidirectional"))
    )
    (net (code "69") (name "SP3_TX") (class "Default")
      (node (ref "P103") (pin "B-4") (pinfunction "3_B-4") (pintype "bidirectional"))
      (node (ref "U402") (pin "21") (pinfunction "T2OUT_21") (pintype "bidirectional"))
    )
    (net (code "70") (name "UART0_1PPS") (class "Default")
      (node (ref "P301") (pin "P$33") (pinfunction "P2-33_P$33") (pintype "bidirectional"))
      (node (ref "U401") (pin "11") (pinfunction "R2OUT_11") (pintype "bidirectional"))
    )
    (net (code "71") (name "UART0_RX") (class "Default")
      (node (ref "P301") (pin "P$29") (pinfunction "P2-29_P$29") (pintype "bidirectional"))
      (node (ref "U401") (pin "10") (pinfunction "R1OUT_10") (pintype "bidirectional"))
    )
    (net (code "72") (name "UART0_TX") (class "Default")
      (node (ref "P301") (pin "P$31") (pinfunction "P2-31_P$31") (pintype "bidirectional"))
      (node (ref "U401") (pin "7") (pinfunction "T1IN_7") (pintype "bidirectional"))
    )
    (net (code "73") (name "UART1_1PPS") (class "Default")
      (node (ref "P301") (pin "P$40") (pinfunction "P2-40_P$40") (pintype "bidirectional"))
      (node (ref "U401") (pin "13") (pinfunction "R4OUT_13") (pintype "bidirectional"))
    )
    (net (code "74") (name "UART1_RX") (class "Default")
      (node (ref "P301") (pin "P$37") (pinfunction "P2-37_P$37") (pintype "bidirectional"))
      (node (ref "U401") (pin "12") (pinfunction "R3OUT_12") (pintype "bidirectional"))
    )
    (net (code "75") (name "UART1_TX") (class "Default")
      (node (ref "P301") (pin "P$39") (pinfunction "P2-39_P$39") (pintype "bidirectional"))
      (node (ref "U401") (pin "8") (pinfunction "T2IN_8") (pintype "bidirectional"))
    )
    (net (code "76") (name "UART2_1PPS") (class "Default")
      (node (ref "P301") (pin "P$50") (pinfunction "P2-50_P$50") (pintype "bidirectional"))
      (node (ref "U402") (pin "11") (pinfunction "R2OUT_11") (pintype "bidirectional"))
    )
    (net (code "77") (name "UART2_RX") (class "Default")
      (node (ref "P301") (pin "P$49") (pinfunction "P2-49_P$49") (pintype "bidirectional"))
      (node (ref "U402") (pin "10") (pinfunction "R1OUT_10") (pintype "bidirectional"))
    )
    (net (code "78") (name "UART2_TX") (class "Default")
      (node (ref "P301") (pin "P$47") (pinfunction "P2-47_P$47") (pintype "bidirectional"))
      (node (ref "U402") (pin "7") (pinfunction "T1IN_7") (pintype "bidirectional"))
    )
    (net (code "79") (name "UART3_1PPS") (class "Default")
      (node (ref "P301") (pin "P$46") (pinfunction "P2-46_P$46") (pintype "bidirectional"))
      (node (ref "U402") (pin "13") (pinfunction "R4OUT_13") (pintype "bidirectional"))
    )
    (net (code "80") (name "UART3_RX") (class "Default")
      (node (ref "P301") (pin "P$41") (pinfunction "P2-41_P$41") (pintype "bidirectional"))
      (node (ref "U402") (pin "12") (pinfunction "R3OUT_12") (pintype "bidirectional"))
    )
    (net (code "81") (name "UART3_TX") (class "Default")
      (node (ref "P301") (pin "P$43") (pinfunction "P2-43_P$43") (pintype "bidirectional"))
      (node (ref "U402") (pin "8") (pinfunction "T2IN_8") (pintype "bidirectional"))
    )
    (net (code "82") (name "USB_D+") (class "Default")
      (node (ref "P301") (pin "P$61") (pinfunction "P2-61_P$61") (pintype "bidirectional"))
      (node (ref "X301") (pin "3") (pinfunction "3_3") (pintype "input"))
    )
    (net (code "83") (name "USB_D-") (class "Default")
      (node (ref "P301") (pin "P$63") (pinfunction "P2-63_P$63") (pintype "bidirectional"))
      (node (ref "X301") (pin "2") (pinfunction "2_2") (pintype "input"))
    )
    (net (code "84") (name "VBATT") (class "Default")
      (node (ref "D201") (pin "A") (pinfunction "A_A") (pintype "passive"))
      (node (ref "P102") (pin "7") (pinfunction "7_7") (pintype "bidirectional"))
    )
    (net (code "85") (name "VBATT_PROTECTED") (class "Default")
      (node (ref "C201") (pin "1") (pinfunction "1_1") (pintype "passive"))
      (node (ref "C202") (pin "1") (pinfunction "1_1") (pintype "passive"))
      (node (ref "D201") (pin "C") (pinfunction "C_C") (pintype "passive"))
      (node (ref "D204") (pin "C") (pinfunction "C_C") (pintype "passive"))
      (node (ref "R210") (pin "1") (pinfunction "1_1") (pintype "passive"))
      (node (ref "U201") (pin "2") (pinfunction "VIN_2") (pintype "bidirectional"))
    )
    (net (code "86") (name "VDD_PGOOD") (class "Default")
      (node (ref "LED201") (pin "A") (pinfunction "A_A") (pintype "passive"))
      (node (ref "R202") (pin "1") (pinfunction "1_1") (pintype "passive"))
      (node (ref "U201") (pin "6") (pinfunction "PWRGD_6") (pintype "bidirectional"))
    )
    (net (code "87") (name "VIGN") (class "Default")
      (node (ref "D1") (pin "1") (pinfunction "A_1") (pintype "passive"))
      (node (ref "D207") (pin "1") (pinfunction "A_1") (pintype "passive"))
      (node (ref "P102") (pin "8") (pinfunction "8_8") (pintype "bidirectional"))
    )
    (net (code "88") (name "XCVR_EN") (class "Default")
      (node (ref "R401") (pin "1") (pinfunction "1_1") (pintype "passive"))
      (node (ref "R407") (pin "1") (pinfunction "1_1") (pintype "passive"))
      (node (ref "U401") (pin "5") (pinfunction "EN_5") (pintype "bidirectional"))
      (node (ref "U402") (pin "5") (pinfunction "EN_5") (pintype "bidirectional"))
    )
    (net (code "89") (name "unconnected-(B401-+1-Pad+2)") (class "Default")
      (node (ref "B401") (pin "+2") (pinfunction "+1_+2") (pintype "passive"))
    )
    (net (code "90") (name "unconnected-(IC401-NC-Pad5)") (class "Default")
      (node (ref "IC401") (pin "5") (pinfunction "NC_5") (pintype "no_connect"))
    )
    (net (code "91") (name "unconnected-(IC401-NC1-Pad6)") (class "Default")
      (node (ref "IC401") (pin "6") (pinfunction "NC1_6") (pintype "no_connect"))
    )
    (net (code "92") (name "unconnected-(IC401-NC2-Pad7)") (class "Default")
      (node (ref "IC401") (pin "7") (pinfunction "NC2_7") (pintype "no_connect"))
    )
    (net (code "93") (name "unconnected-(IC401-NC3-Pad8)") (class "Default")
      (node (ref "IC401") (pin "8") (pinfunction "NC3_8") (pintype "no_connect"))
    )
    (net (code "94") (name "unconnected-(IC401-NC4-Pad9)") (class "Default")
      (node (ref "IC401") (pin "9") (pinfunction "NC4_9") (pintype "no_connect"))
    )
    (net (code "95") (name "unconnected-(IC401-NC5-Pad10)") (class "Default")
      (node (ref "IC401") (pin "10") (pinfunction "NC5_10") (pintype "no_connect"))
    )
    (net (code "96") (name "unconnected-(IC401-NC6-Pad11)") (class "Default")
      (node (ref "IC401") (pin "11") (pinfunction "NC6_11") (pintype "no_connect"))
    )
    (net (code "97") (name "unconnected-(IC401-NC7-Pad12)") (class "Default")
      (node (ref "IC401") (pin "12") (pinfunction "NC7_12") (pintype "no_connect"))
    )
    (net (code "98") (name "unconnected-(IC401-SQW{slash}INT-Pad3)") (class "Default")
      (node (ref "IC401") (pin "3") (pinfunction "SQW/INT_3") (pintype "output"))
    )
    (net (code "99") (name "unconnected-(P101A-4-PadA-4)") (class "Default")
      (node (ref "P101") (pin "A-4") (pinfunction "4_A-4") (pintype "bidirectional"))
    )
    (net (code "100") (name "unconnected-(P101A-6-PadA-6)") (class "Default")
      (node (ref "P101") (pin "A-6") (pinfunction "6_A-6") (pintype "bidirectional"))
    )
    (net (code "101") (name "unconnected-(P101A-7-PadA-7)") (class "Default")
      (node (ref "P101") (pin "A-7") (pinfunction "7_A-7") (pintype "bidirectional"))
    )
    (net (code "102") (name "unconnected-(P101A-8-PadA-8)") (class "Default")
      (node (ref "P101") (pin "A-8") (pinfunction "8_A-8") (pintype "bidirectional"))
    )
    (net (code "103") (name "unconnected-(P101A-9-PadA-9)") (class "Default")
      (node (ref "P101") (pin "A-9") (pinfunction "9_A-9") (pintype "bidirectional"))
    )
    (net (code "104") (name "unconnected-(P101B-4-PadB-5)") (class "Default")
      (node (ref "P101") (pin "B-5") (pinfunction "4_B-5") (pintype "bidirectional"))
    )
    (net (code "105") (name "unconnected-(P101B-6-PadP$1)") (class "Default")
      (node (ref "P101") (pin "P$1") (pinfunction "6_P$1") (pintype "bidirectional"))
    )
    (net (code "106") (name "unconnected-(P101B-7-PadP$2)") (class "Default")
      (node (ref "P101") (pin "P$2") (pinfunction "7_P$2") (pintype "bidirectional"))
    )
    (net (code "107") (name "unconnected-(P101B-8-PadP$3)") (class "Default")
      (node (ref "P101") (pin "P$3") (pinfunction "8_P$3") (pintype "bidirectional"))
    )
    (net (code "108") (name "unconnected-(P101B-9-PadP$4)") (class "Default")
      (node (ref "P101") (pin "P$4") (pinfunction "9_P$4") (pintype "bidirectional"))
    )
    (net (code "109") (name "unconnected-(P103A-4-PadA-4)") (class "Default")
      (node (ref "P103") (pin "A-4") (pinfunction "4_A-4") (pintype "bidirectional"))
    )
    (net (code "110") (name "unconnected-(P103A-6-PadA-6)") (class "Default")
      (node (ref "P103") (pin "A-6") (pinfunction "6_A-6") (pintype "bidirectional"))
    )
    (net (code "111") (name "unconnected-(P103A-7-PadA-7)") (class "Default")
      (node (ref "P103") (pin "A-7") (pinfunction "7_A-7") (pintype "bidirectional"))
    )
    (net (code "112") (name "unconnected-(P103A-8-PadA-8)") (class "Default")
      (node (ref "P103") (pin "A-8") (pinfunction "8_A-8") (pintype "bidirectional"))
    )
    (net (code "113") (name "unconnected-(P103A-9-PadA-9)") (class "Default")
      (node (ref "P103") (pin "A-9") (pinfunction "9_A-9") (pintype "bidirectional"))
    )
    (net (code "114") (name "unconnected-(P103B-4-PadB-5)") (class "Default")
      (node (ref "P103") (pin "B-5") (pinfunction "4_B-5") (pintype "bidirectional"))
    )
    (net (code "115") (name "unconnected-(P103B-6-PadP$1)") (class "Default")
      (node (ref "P103") (pin "P$1") (pinfunction "6_P$1") (pintype "bidirectional"))
    )
    (net (code "116") (name "unconnected-(P103B-7-PadP$2)") (class "Default")
      (node (ref "P103") (pin "P$2") (pinfunction "7_P$2") (pintype "bidirectional"))
    )
    (net (code "117") (name "unconnected-(P103B-8-PadP$3)") (class "Default")
      (node (ref "P103") (pin "P$3") (pinfunction "8_P$3") (pintype "bidirectional"))
    )
    (net (code "118") (name "unconnected-(P103B-9-PadP$4)") (class "Default")
      (node (ref "P103") (pin "P$4") (pinfunction "9_P$4") (pintype "bidirectional"))
    )
    (net (code "119") (name "unconnected-(P301-P2-5-PadP$5)") (class "Default")
      (node (ref "P301") (pin "P$5") (pinfunction "P2-5_P$5") (pintype "bidirectional"))
    )
    (net (code "120") (name "unconnected-(P301-P2-7-PadP$7)") (class "Default")
      (node (ref "P301") (pin "P$7") (pinfunction "P2-7_P$7") (pintype "bidirectional"))
    )
    (net (code "121") (name "unconnected-(P301-P2-14-PadP$14)") (class "Default")
      (node (ref "P301") (pin "P$14") (pinfunction "P2-14_P$14") (pintype "bidirectional"))
    )
    (net (code "122") (name "unconnected-(P301-P2-15-PadP$15)") (class "Default")
      (node (ref "P301") (pin "P$15") (pinfunction "P2-15_P$15") (pintype "bidirectional"))
    )
    (net (code "123") (name "unconnected-(P301-P2-16-PadP$16)") (class "Default")
      (node (ref "P301") (pin "P$16") (pinfunction "P2-16_P$16") (pintype "bidirectional"))
    )
    (net (code "124") (name "unconnected-(P301-P2-17-PadP$17)") (class "Default")
      (node (ref "P301") (pin "P$17") (pinfunction "P2-17_P$17") (pintype "bidirectional"))
    )
    (net (code "125") (name "unconnected-(P301-P2-18-PadP$18)") (class "Default")
      (node (ref "P301") (pin "P$18") (pinfunction "P2-18_P$18") (pintype "bidirectional"))
    )
    (net (code "126") (name "unconnected-(P301-P2-19-PadP$19)") (class "Default")
      (node (ref "P301") (pin "P$19") (pinfunction "P2-19_P$19") (pintype "bidirectional"))
    )
    (net (code "127") (name "unconnected-(P301-P2-20-PadP$20)") (class "Default")
      (node (ref "P301") (pin "P$20") (pinfunction "P2-20_P$20") (pintype "bidirectional"))
    )
    (net (code "128") (name "unconnected-(P301-P2-21-PadP$21)") (class "Default")
      (node (ref "P301") (pin "P$21") (pinfunction "P2-21_P$21") (pintype "bidirectional"))
    )
    (net (code "129") (name "unconnected-(P301-P2-22-PadP$22)") (class "Default")
      (node (ref "P301") (pin "P$22") (pinfunction "P2-22_P$22") (pintype "bidirectional"))
    )
    (net (code "130") (name "unconnected-(P301-P2-23-PadP$23)") (class "Default")
      (node (ref "P301") (pin "P$23") (pinfunction "P2-23_P$23") (pintype "bidirectional"))
    )
    (net (code "131") (name "unconnected-(P301-P2-24-PadP$24)") (class "Default")
      (node (ref "P301") (pin "P$24") (pinfunction "P2-24_P$24") (pintype "bidirectional"))
    )
    (net (code "132") (name "unconnected-(P301-P2-25-PadP$25)") (class "Default")
      (node (ref "P301") (pin "P$25") (pinfunction "P2-25_P$25") (pintype "bidirectional"))
    )
    (net (code "133") (name "unconnected-(P301-P2-26-PadP$26)") (class "Default")
      (node (ref "P301") (pin "P$26") (pinfunction "P2-26_P$26") (pintype "bidirectional"))
    )
    (net (code "134") (name "unconnected-(P301-P2-28-PadP$28)") (class "Default")
      (node (ref "P301") (pin "P$28") (pinfunction "P2-28_P$28") (pintype "bidirectional"))
    )
    (net (code "135") (name "unconnected-(P301-P2-30-PadP$30)") (class "Default")
      (node (ref "P301") (pin "P$30") (pinfunction "P2-30_P$30") (pintype "bidirectional"))
    )
    (net (code "136") (name "unconnected-(P301-P2-32-PadP$32)") (class "Default")
      (node (ref "P301") (pin "P$32") (pinfunction "P2-32_P$32") (pintype "bidirectional"))
    )
    (net (code "137") (name "unconnected-(P301-P2-34-PadP$34)") (class "Default")
      (node (ref "P301") (pin "P$34") (pinfunction "P2-34_P$34") (pintype "bidirectional"))
    )
    (net (code "138") (name "unconnected-(P301-P2-35-PadP$35)") (class "Default")
      (node (ref "P301") (pin "P$35") (pinfunction "P2-35_P$35") (pintype "bidirectional"))
    )
    (net (code "139") (name "unconnected-(P301-P2-36-PadP$36)") (class "Default")
      (node (ref "P301") (pin "P$36") (pinfunction "P2-36_P$36") (pintype "bidirectional"))
    )
    (net (code "140") (name "unconnected-(P301-P2-42-PadP$42)") (class "Default")
      (node (ref "P301") (pin "P$42") (pinfunction "P2-42_P$42") (pintype "bidirectional"))
    )
    (net (code "141") (name "unconnected-(P301-P2-44-PadP$44)") (class "Default")
      (node (ref "P301") (pin "P$44") (pinfunction "P2-44_P$44") (pintype "bidirectional"))
    )
    (net (code "142") (name "unconnected-(P301-P2-45-PadP$45)") (class "Default")
      (node (ref "P301") (pin "P$45") (pinfunction "P2-45_P$45") (pintype "bidirectional"))
    )
    (net (code "143") (name "unconnected-(P301-P2-48-PadP$48)") (class "Default")
      (node (ref "P301") (pin "P$48") (pinfunction "P2-48_P$48") (pintype "bidirectional"))
    )
    (net (code "144") (name "unconnected-(P301-P2-51-PadP$51)") (class "Default")
      (node (ref "P301") (pin "P$51") (pinfunction "P2-51_P$51") (pintype "bidirectional"))
    )
    (net (code "145") (name "unconnected-(P301-P2-52-PadP$52)") (class "Default")
      (node (ref "P301") (pin "P$52") (pinfunction "P2-52_P$52") (pintype "bidirectional"))
    )
    (net (code "146") (name "unconnected-(P301-P2-53-PadP$53)") (class "Default")
      (node (ref "P301") (pin "P$53") (pinfunction "P2-53_P$53") (pintype "bidirectional"))
    )
    (net (code "147") (name "unconnected-(P301-P2-54-PadP$54)") (class "Default")
      (node (ref "P301") (pin "P$54") (pinfunction "P2-54_P$54") (pintype "bidirectional"))
    )
    (net (code "148") (name "unconnected-(P301-P2-55-PadP$55)") (class "Default")
      (node (ref "P301") (pin "P$55") (pinfunction "P2-55_P$55") (pintype "bidirectional"))
    )
    (net (code "149") (name "unconnected-(P301-P2-56-PadP$56)") (class "Default")
      (node (ref "P301") (pin "P$56") (pinfunction "P2-56_P$56") (pintype "bidirectional"))
    )
    (net (code "150") (name "unconnected-(P301-P2-57-PadP$57)") (class "Default")
      (node (ref "P301") (pin "P$57") (pinfunction "P2-57_P$57") (pintype "bidirectional"))
    )
    (net (code "151") (name "unconnected-(P301-P2-58-PadP$58)") (class "Default")
      (node (ref "P301") (pin "P$58") (pinfunction "P2-58_P$58") (pintype "bidirectional"))
    )
    (net (code "152") (name "unconnected-(P301-P3-1-PadP$71)") (class "Default")
      (node (ref "P301") (pin "P$71") (pinfunction "P3-1_P$71") (pintype "bidirectional"))
    )
    (net (code "153") (name "unconnected-(P301-P3-2-PadP$72)") (class "Default")
      (node (ref "P301") (pin "P$72") (pinfunction "P3-2_P$72") (pintype "bidirectional"))
    )
    (net (code "154") (name "unconnected-(P301-P3-3-PadP$73)") (class "Default")
      (node (ref "P301") (pin "P$73") (pinfunction "P3-3_P$73") (pintype "bidirectional"))
    )
    (net (code "155") (name "unconnected-(P301-P3-4-PadP$74)") (class "Default")
      (node (ref "P301") (pin "P$74") (pinfunction "P3-4_P$74") (pintype "bidirectional"))
    )
    (net (code "156") (name "unconnected-(P301-P3-5-PadP$75)") (class "Default")
      (node (ref "P301") (pin "P$75") (pinfunction "P3-5_P$75") (pintype "bidirectional"))
    )
    (net (code "157") (name "unconnected-(P301-P3-6-PadP$76)") (class "Default")
      (node (ref "P301") (pin "P$76") (pinfunction "P3-6_P$76") (pintype "bidirectional"))
    )
    (net (code "158") (name "unconnected-(P301-P3-7-PadP$77)") (class "Default")
      (node (ref "P301") (pin "P$77") (pinfunction "P3-7_P$77") (pintype "bidirectional"))
    )
    (net (code "159") (name "unconnected-(P301-P3-8-PadP$78)") (class "Default")
      (node (ref "P301") (pin "P$78") (pinfunction "P3-8_P$78") (pintype "bidirectional"))
    )
    (net (code "160") (name "unconnected-(P301-P3-9-PadP$79)") (class "Default")
      (node (ref "P301") (pin "P$79") (pinfunction "P3-9_P$79") (pintype "bidirectional"))
    )
    (net (code "161") (name "unconnected-(P301-P3-10-PadP$80)") (class "Default")
      (node (ref "P301") (pin "P$80") (pinfunction "P3-10_P$80") (pintype "bidirectional"))
    )
    (net (code "162") (name "unconnected-(P301-P3-11-PadP$81)") (class "Default")
      (node (ref "P301") (pin "P$81") (pinfunction "P3-11_P$81") (pintype "bidirectional"))
    )
    (net (code "163") (name "unconnected-(P301-P3-12-PadP$82)") (class "Default")
      (node (ref "P301") (pin "P$82") (pinfunction "P3-12_P$82") (pintype "bidirectional"))
    )
    (net (code "164") (name "unconnected-(P301-P3-13-PadP$83)") (class "Default")
      (node (ref "P301") (pin "P$83") (pinfunction "P3-13_P$83") (pintype "bidirectional"))
    )
    (net (code "165") (name "unconnected-(P301-P3-14-PadP$84)") (class "Default")
      (node (ref "P301") (pin "P$84") (pinfunction "P3-14_P$84") (pintype "bidirectional"))
    )
    (net (code "166") (name "unconnected-(P301-P3-15-PadP$85)") (class "Default")
      (node (ref "P301") (pin "P$85") (pinfunction "P3-15_P$85") (pintype "bidirectional"))
    )
    (net (code "167") (name "unconnected-(P301-P3-16-PadP$86)") (class "Default")
      (node (ref "P301") (pin "P$86") (pinfunction "P3-16_P$86") (pintype "bidirectional"))
    )
    (net (code "168") (name "unconnected-(P301-P3-17-PadP$87)") (class "Default")
      (node (ref "P301") (pin "P$87") (pinfunction "P3-17_P$87") (pintype "bidirectional"))
    )
    (net (code "169") (name "unconnected-(P301-P3-18-PadP$88)") (class "Default")
      (node (ref "P301") (pin "P$88") (pinfunction "P3-18_P$88") (pintype "bidirectional"))
    )
    (net (code "170") (name "unconnected-(P301-P3-19-PadP$89)") (class "Default")
      (node (ref "P301") (pin "P$89") (pinfunction "P3-19_P$89") (pintype "bidirectional"))
    )
    (net (code "171") (name "unconnected-(P301-P3-20-PadP$90)") (class "Default")
      (node (ref "P301") (pin "P$90") (pinfunction "P3-20_P$90") (pintype "bidirectional"))
    )
    (net (code "172") (name "unconnected-(P301-P3-23-PadP$93)") (class "Default")
      (node (ref "P301") (pin "P$93") (pinfunction "P3-23_P$93") (pintype "bidirectional"))
    )
    (net (code "173") (name "unconnected-(P301-P3-24-PadP$94)") (class "Default")
      (node (ref "P301") (pin "P$94") (pinfunction "P3-24_P$94") (pintype "bidirectional"))
    )
    (net (code "174") (name "unconnected-(P301-P3-25-PadP$95)") (class "Default")
      (node (ref "P301") (pin "P$95") (pinfunction "P3-25_P$95") (pintype "bidirectional"))
    )
    (net (code "175") (name "unconnected-(P301-P3-26-PadP$96)") (class "Default")
      (node (ref "P301") (pin "P$96") (pinfunction "P3-26_P$96") (pintype "bidirectional"))
    )
    (net (code "176") (name "unconnected-(P301-P3-27-PadP$97)") (class "Default")
      (node (ref "P301") (pin "P$97") (pinfunction "P3-27_P$97") (pintype "bidirectional"))
    )
    (net (code "177") (name "unconnected-(P301-P3-28-PadP$98)") (class "Default")
      (node (ref "P301") (pin "P$98") (pinfunction "P3-28_P$98") (pintype "bidirectional"))
    )
    (net (code "178") (name "unconnected-(P301-P3-29-PadP$99)") (class "Default")
      (node (ref "P301") (pin "P$99") (pinfunction "P3-29_P$99") (pintype "bidirectional"))
    )
    (net (code "179") (name "unconnected-(P301-P3-30-PadP$100)") (class "Default")
      (node (ref "P301") (pin "P$100") (pinfunction "P3-30_P$100") (pintype "bidirectional"))
    )
    (net (code "180") (name "unconnected-(P301-P3-31-PadP$101)") (class "Default")
      (node (ref "P301") (pin "P$101") (pinfunction "P3-31_P$101") (pintype "bidirectional"))
    )
    (net (code "181") (name "unconnected-(P301-P3-32-PadP$102)") (class "Default")
      (node (ref "P301") (pin "P$102") (pinfunction "P3-32_P$102") (pintype "bidirectional"))
    )
    (net (code "182") (name "unconnected-(P301-P3-33-PadP$103)") (class "Default")
      (node (ref "P301") (pin "P$103") (pinfunction "P3-33_P$103") (pintype "bidirectional"))
    )
    (net (code "183") (name "unconnected-(P301-P3-34-PadP$104)") (class "Default")
      (node (ref "P301") (pin "P$104") (pinfunction "P3-34_P$104") (pintype "bidirectional"))
    )
    (net (code "184") (name "unconnected-(P301-P3-35-PadP$105)") (class "Default")
      (node (ref "P301") (pin "P$105") (pinfunction "P3-35_P$105") (pintype "bidirectional"))
    )
    (net (code "185") (name "unconnected-(P301-P3-36-PadP$106)") (class "Default")
      (node (ref "P301") (pin "P$106") (pinfunction "P3-36_P$106") (pintype "bidirectional"))
    )
    (net (code "186") (name "unconnected-(P301-P3-37-PadP$107)") (class "Default")
      (node (ref "P301") (pin "P$107") (pinfunction "P3-37_P$107") (pintype "bidirectional"))
    )
    (net (code "187") (name "unconnected-(P301-P3-38-PadP$108)") (class "Default")
      (node (ref "P301") (pin "P$108") (pinfunction "P3-38_P$108") (pintype "bidirectional"))
    )
    (net (code "188") (name "unconnected-(P301-P3-39-PadP$109)") (class "Default")
      (node (ref "P301") (pin "P$109") (pinfunction "P3-39_P$109") (pintype "bidirectional"))
    )
    (net (code "189") (name "unconnected-(P301-P3-40-PadP$110)") (class "Default")
      (node (ref "P301") (pin "P$110") (pinfunction "P3-40_P$110") (pintype "bidirectional"))
    )
    (net (code "190") (name "unconnected-(P301-P3-41-PadP$111)") (class "Default")
      (node (ref "P301") (pin "P$111") (pinfunction "P3-41_P$111") (pintype "bidirectional"))
    )
    (net (code "191") (name "unconnected-(P301-P3-42-PadP$112)") (class "Default")
      (node (ref "P301") (pin "P$112") (pinfunction "P3-42_P$112") (pintype "bidirectional"))
    )
    (net (code "192") (name "unconnected-(P301-P3-43-PadP$113)") (class "Default")
      (node (ref "P301") (pin "P$113") (pinfunction "P3-43_P$113") (pintype "bidirectional"))
    )
    (net (code "193") (name "unconnected-(P301-P3-44-PadP$114)") (class "Default")
      (node (ref "P301") (pin "P$114") (pinfunction "P3-44_P$114") (pintype "bidirectional"))
    )
    (net (code "194") (name "unconnected-(P301-P3-45-PadP$115)") (class "Default")
      (node (ref "P301") (pin "P$115") (pinfunction "P3-45_P$115") (pintype "bidirectional"))
    )
    (net (code "195") (name "unconnected-(P301-P3-46-PadP$116)") (class "Default")
      (node (ref "P301") (pin "P$116") (pinfunction "P3-46_P$116") (pintype "bidirectional"))
    )
    (net (code "196") (name "unconnected-(P301-P3-47-PadP$117)") (class "Default")
      (node (ref "P301") (pin "P$117") (pinfunction "P3-47_P$117") (pintype "bidirectional"))
    )
    (net (code "197") (name "unconnected-(P301-P3-48-PadP$118)") (class "Default")
      (node (ref "P301") (pin "P$118") (pinfunction "P3-48_P$118") (pintype "bidirectional"))
    )
    (net (code "198") (name "unconnected-(P301-P3-49-PadP$119)") (class "Default")
      (node (ref "P301") (pin "P$119") (pinfunction "P3-49_P$119") (pintype "bidirectional"))
    )
    (net (code "199") (name "unconnected-(P301-P3-50-PadP$120)") (class "Default")
      (node (ref "P301") (pin "P$120") (pinfunction "P3-50_P$120") (pintype "bidirectional"))
    )
    (net (code "200") (name "unconnected-(P301-P3-51-PadP$121)") (class "Default")
      (node (ref "P301") (pin "P$121") (pinfunction "P3-51_P$121") (pintype "bidirectional"))
    )
    (net (code "201") (name "unconnected-(P301-P3-52-PadP$122)") (class "Default")
      (node (ref "P301") (pin "P$122") (pinfunction "P3-52_P$122") (pintype "bidirectional"))
    )
    (net (code "202") (name "unconnected-(P301-P3-53-PadP$123)") (class "Default")
      (node (ref "P301") (pin "P$123") (pinfunction "P3-53_P$123") (pintype "bidirectional"))
    )
    (net (code "203") (name "unconnected-(P301-P3-54-PadP$124)") (class "Default")
      (node (ref "P301") (pin "P$124") (pinfunction "P3-54_P$124") (pintype "bidirectional"))
    )
    (net (code "204") (name "unconnected-(P301-P3-55-PadP$125)") (class "Default")
      (node (ref "P301") (pin "P$125") (pinfunction "P3-55_P$125") (pintype "bidirectional"))
    )
    (net (code "205") (name "unconnected-(P301-P3-56-PadP$126)") (class "Default")
      (node (ref "P301") (pin "P$126") (pinfunction "P3-56_P$126") (pintype "bidirectional"))
    )
    (net (code "206") (name "unconnected-(P301-P3-57-PadP$127)") (class "Default")
      (node (ref "P301") (pin "P$127") (pinfunction "P3-57_P$127") (pintype "bidirectional"))
    )
    (net (code "207") (name "unconnected-(P301-P3-58-PadP$128)") (class "Default")
      (node (ref "P301") (pin "P$128") (pinfunction "P3-58_P$128") (pintype "bidirectional"))
    )
    (net (code "208") (name "unconnected-(P301-P3-60-PadP$130)") (class "Default")
      (node (ref "P301") (pin "P$130") (pinfunction "P3-60_P$130") (pintype "bidirectional"))
    )
    (net (code "209") (name "unconnected-(P301-P3-61-PadP$131)") (class "Default")
      (node (ref "P301") (pin "P$131") (pinfunction "P3-61_P$131") (pintype "bidirectional"))
    )
    (net (code "210") (name "unconnected-(P301-P3-62-PadP$132)") (class "Default")
      (node (ref "P301") (pin "P$132") (pinfunction "P3-62_P$132") (pintype "bidirectional"))
    )
    (net (code "211") (name "unconnected-(P301-P3-63-PadP$133)") (class "Default")
      (node (ref "P301") (pin "P$133") (pinfunction "P3-63_P$133") (pintype "bidirectional"))
    )
    (net (code "212") (name "unconnected-(P301-P3-64-PadP$134)") (class "Default")
      (node (ref "P301") (pin "P$134") (pinfunction "P3-64_P$134") (pintype "bidirectional"))
    )
    (net (code "213") (name "unconnected-(P301-P3-66-PadP$136)") (class "Default")
      (node (ref "P301") (pin "P$136") (pinfunction "P3-66_P$136") (pintype "bidirectional"))
    )
    (net (code "214") (name "unconnected-(P301-P3-67-PadP$137)") (class "Default")
      (node (ref "P301") (pin "P$137") (pinfunction "P3-67_P$137") (pintype "bidirectional"))
    )
    (net (code "215") (name "unconnected-(P301-P3-68-PadP$138)") (class "Default")
      (node (ref "P301") (pin "P$138") (pinfunction "P3-68_P$138") (pintype "bidirectional"))
    )
    (net (code "216") (name "unconnected-(P301-P3-69-PadP$139)") (class "Default")
      (node (ref "P301") (pin "P$139") (pinfunction "P3-69_P$139") (pintype "bidirectional"))
    )
    (net (code "217") (name "unconnected-(P301-P3-70-PadP$140)") (class "Default")
      (node (ref "P301") (pin "P$140") (pinfunction "P3-70_P$140") (pintype "bidirectional"))
    )
    (net (code "218") (name "unconnected-(X301-Pad1)") (class "Default")
      (node (ref "X301") (pin "1") (pinfunction "1_1") (pintype "input"))
    )
    (net (code "219") (name "unconnected-(X301-Pad4)") (class "Default")
      (node (ref "X301") (pin "4") (pinfunction "4_4") (pintype "input"))
    )
  )
)
